# io-board-d-6.net
KiCad netlist of a schematic drawn in EAGLE
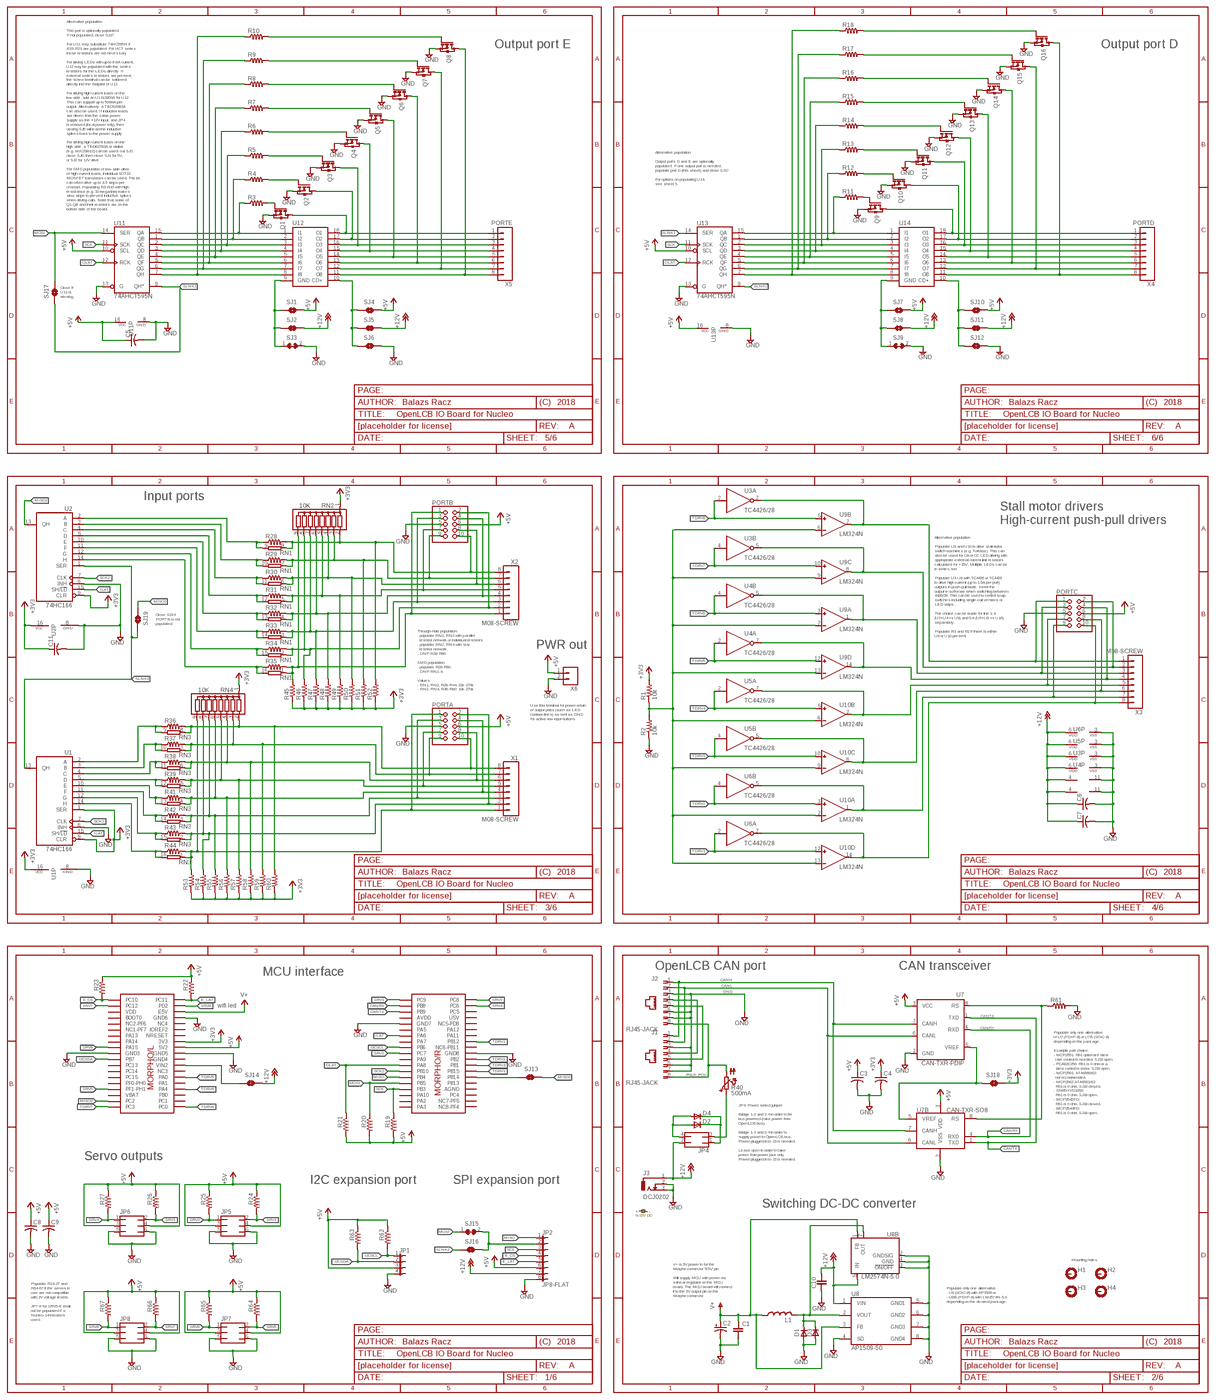
[diagram p0: schematic, sheet 1, overview]
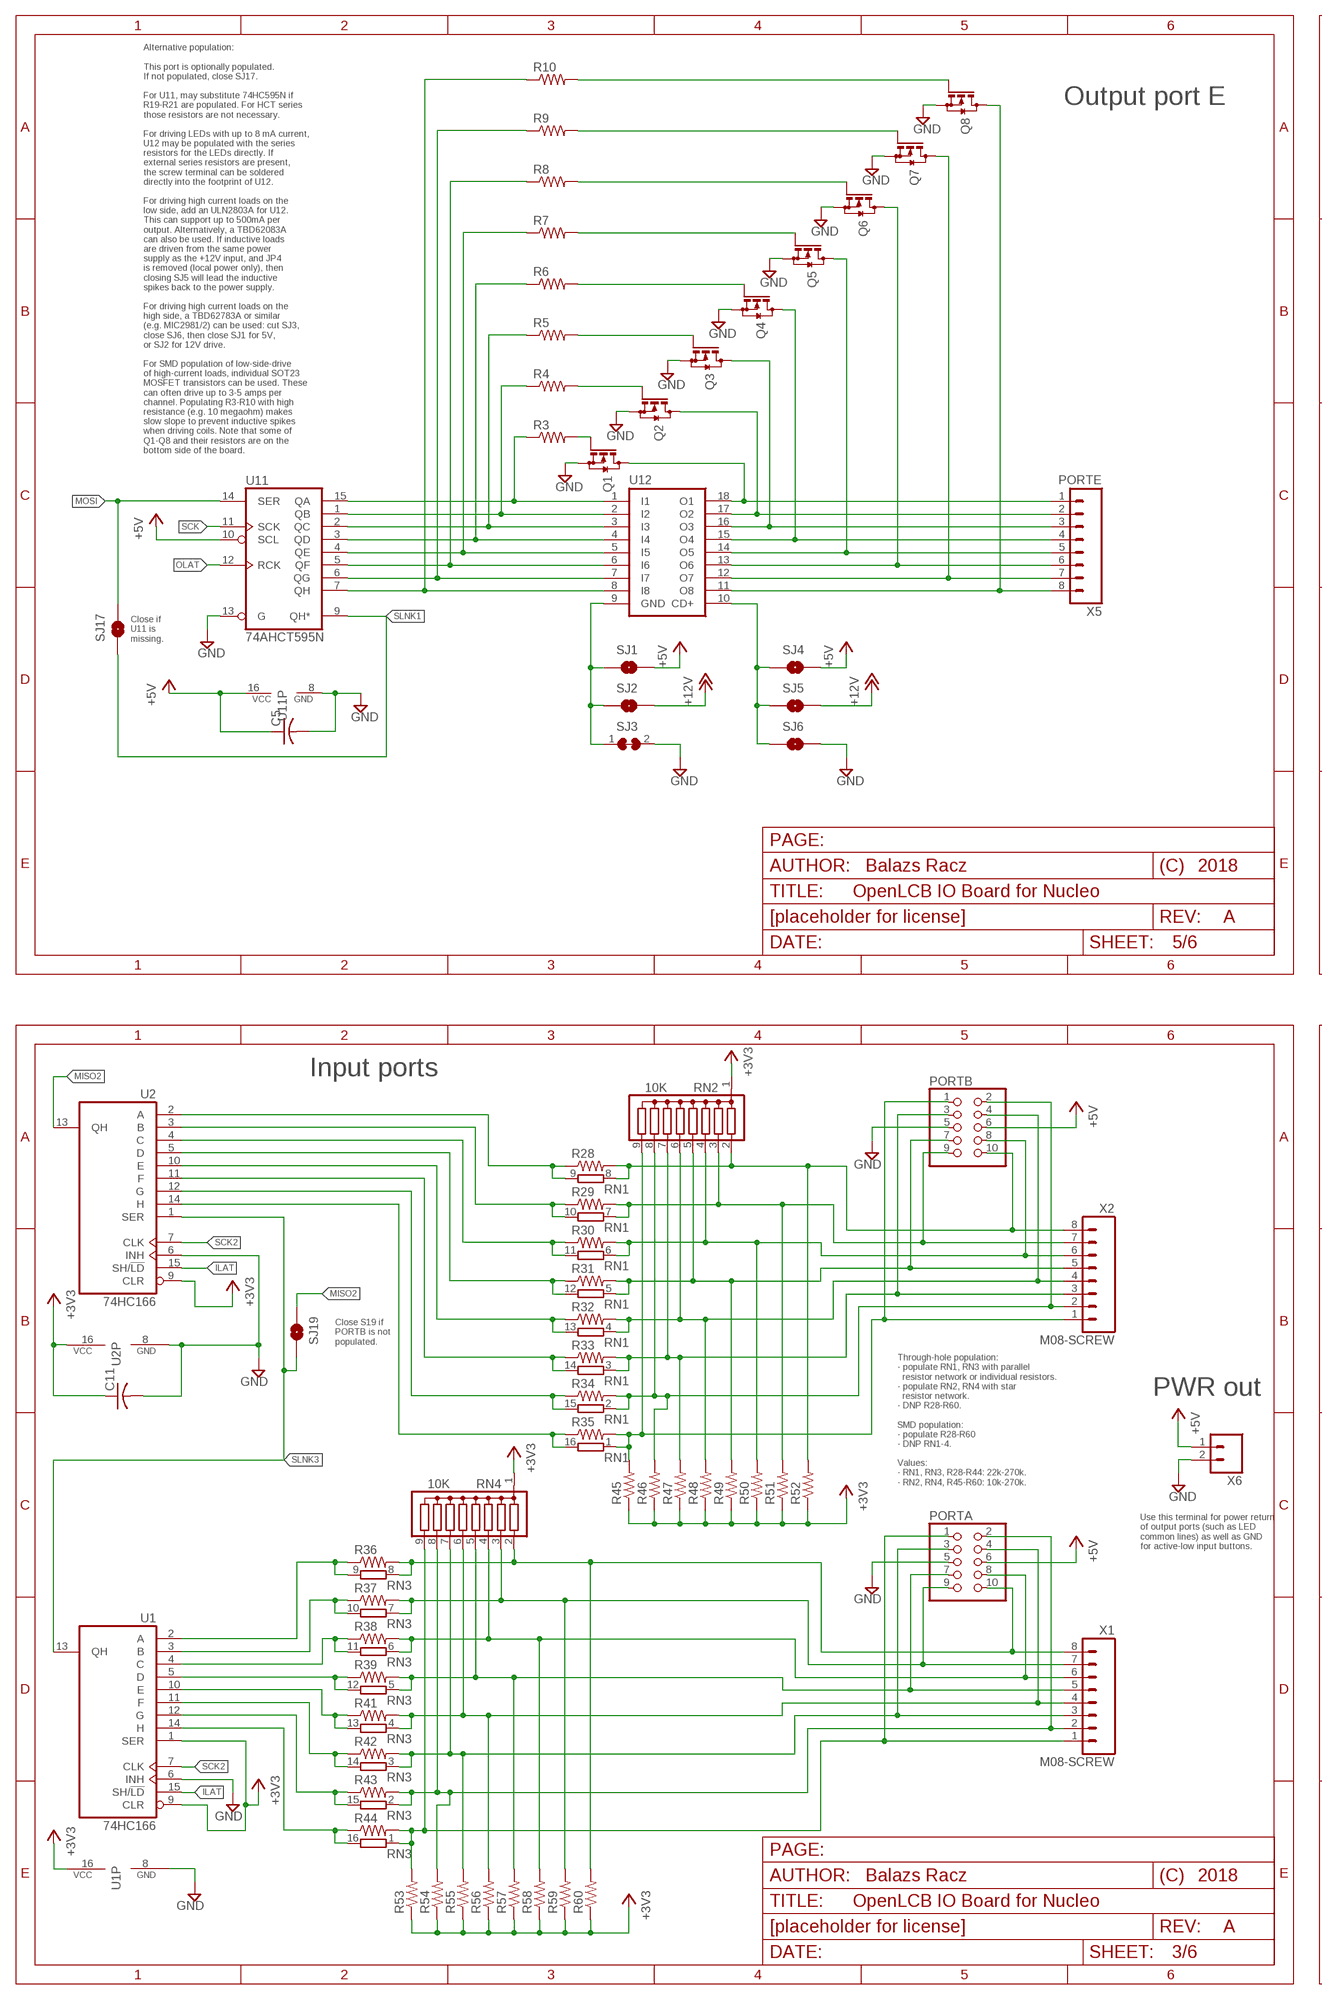
[diagram p1: schematic, sheet 1, part 1 of 4]
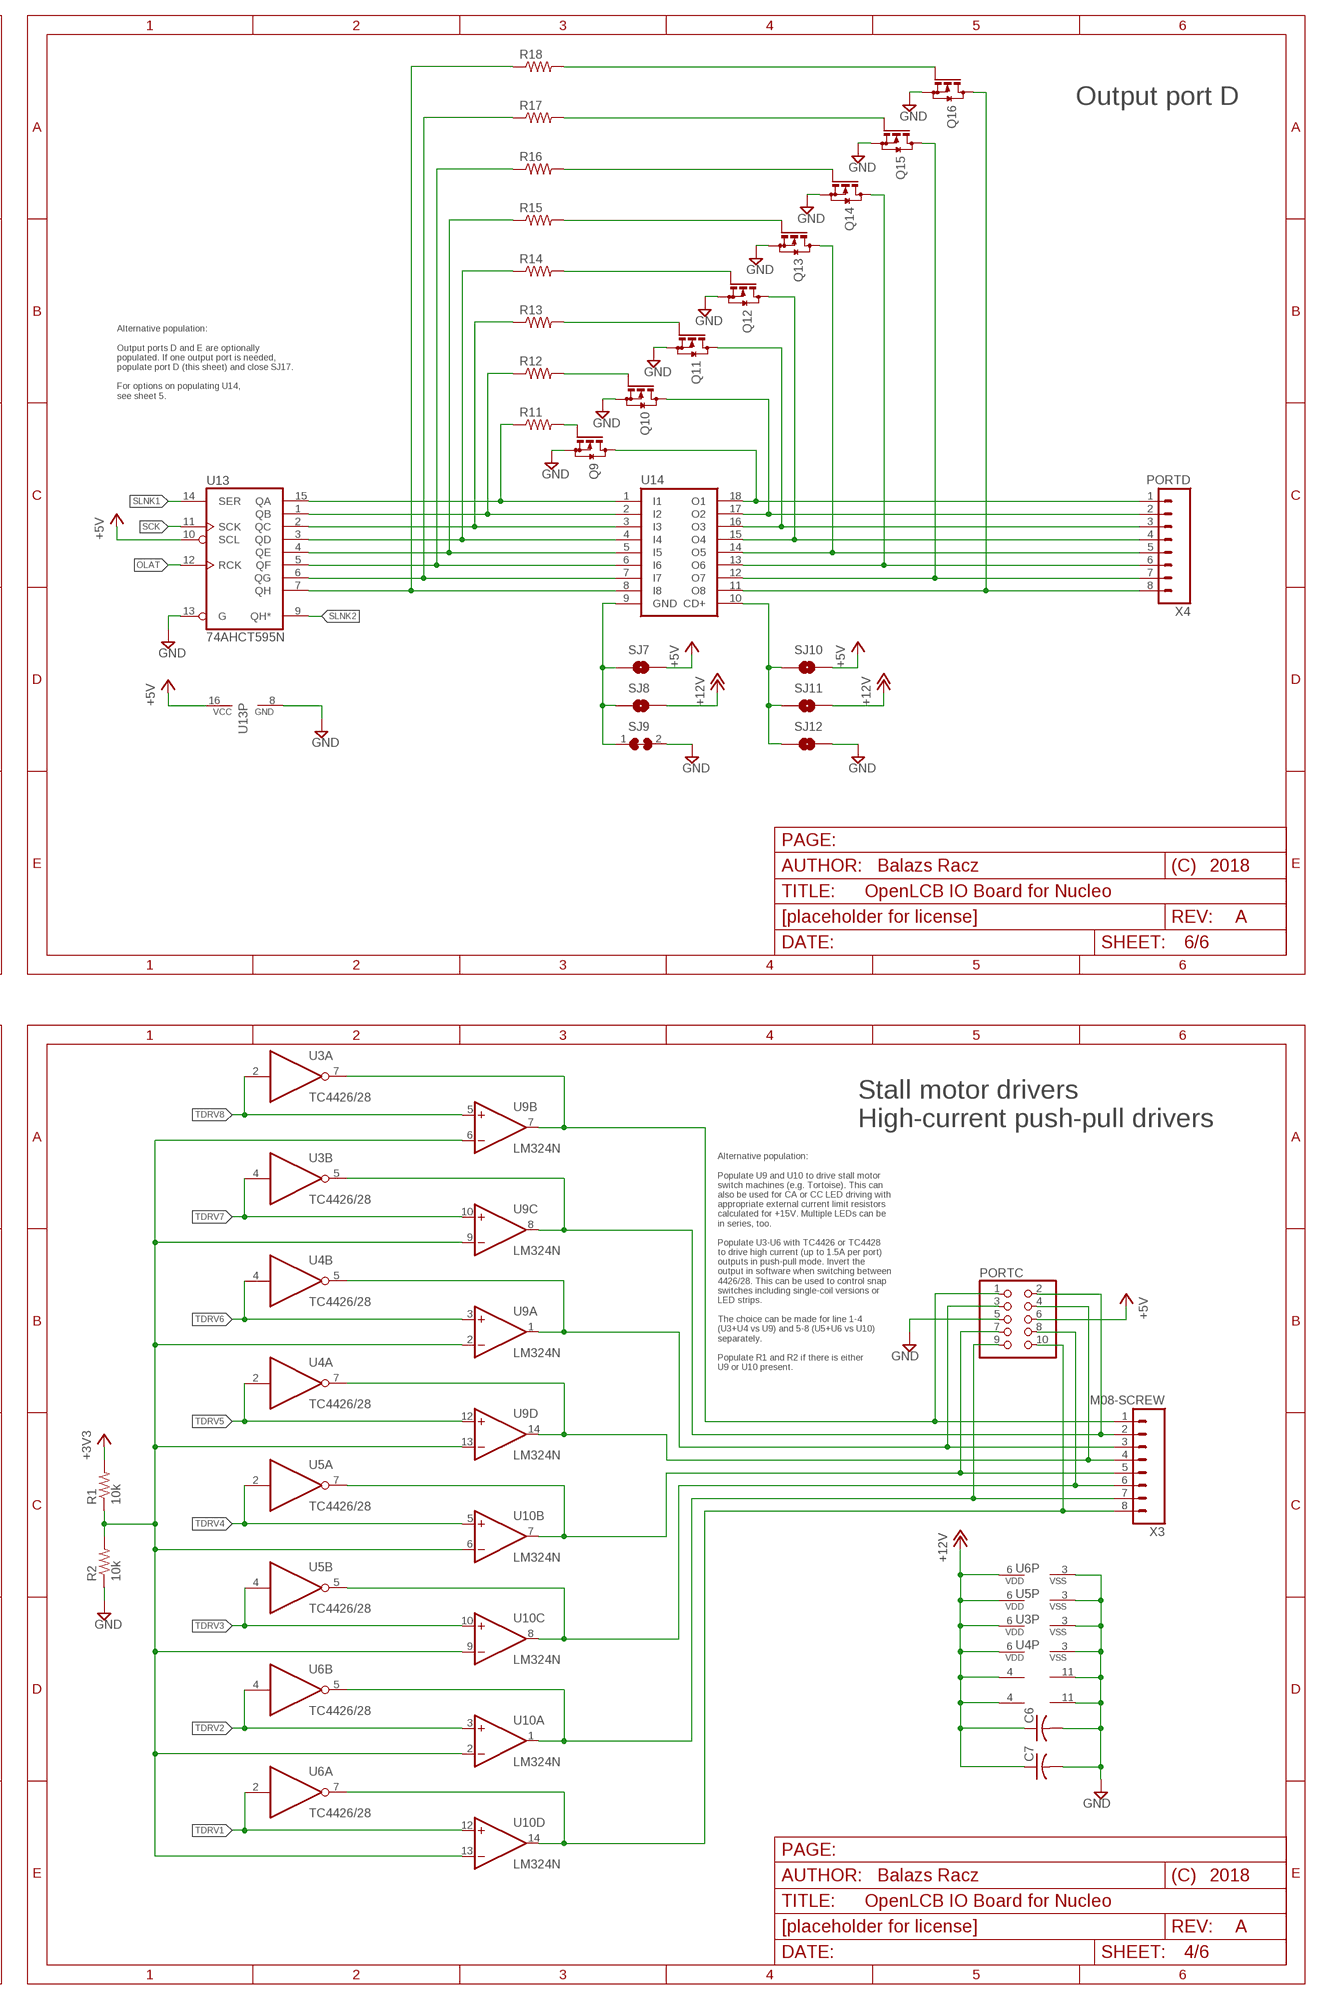
[diagram p2: schematic, sheet 1, part 2 of 4]
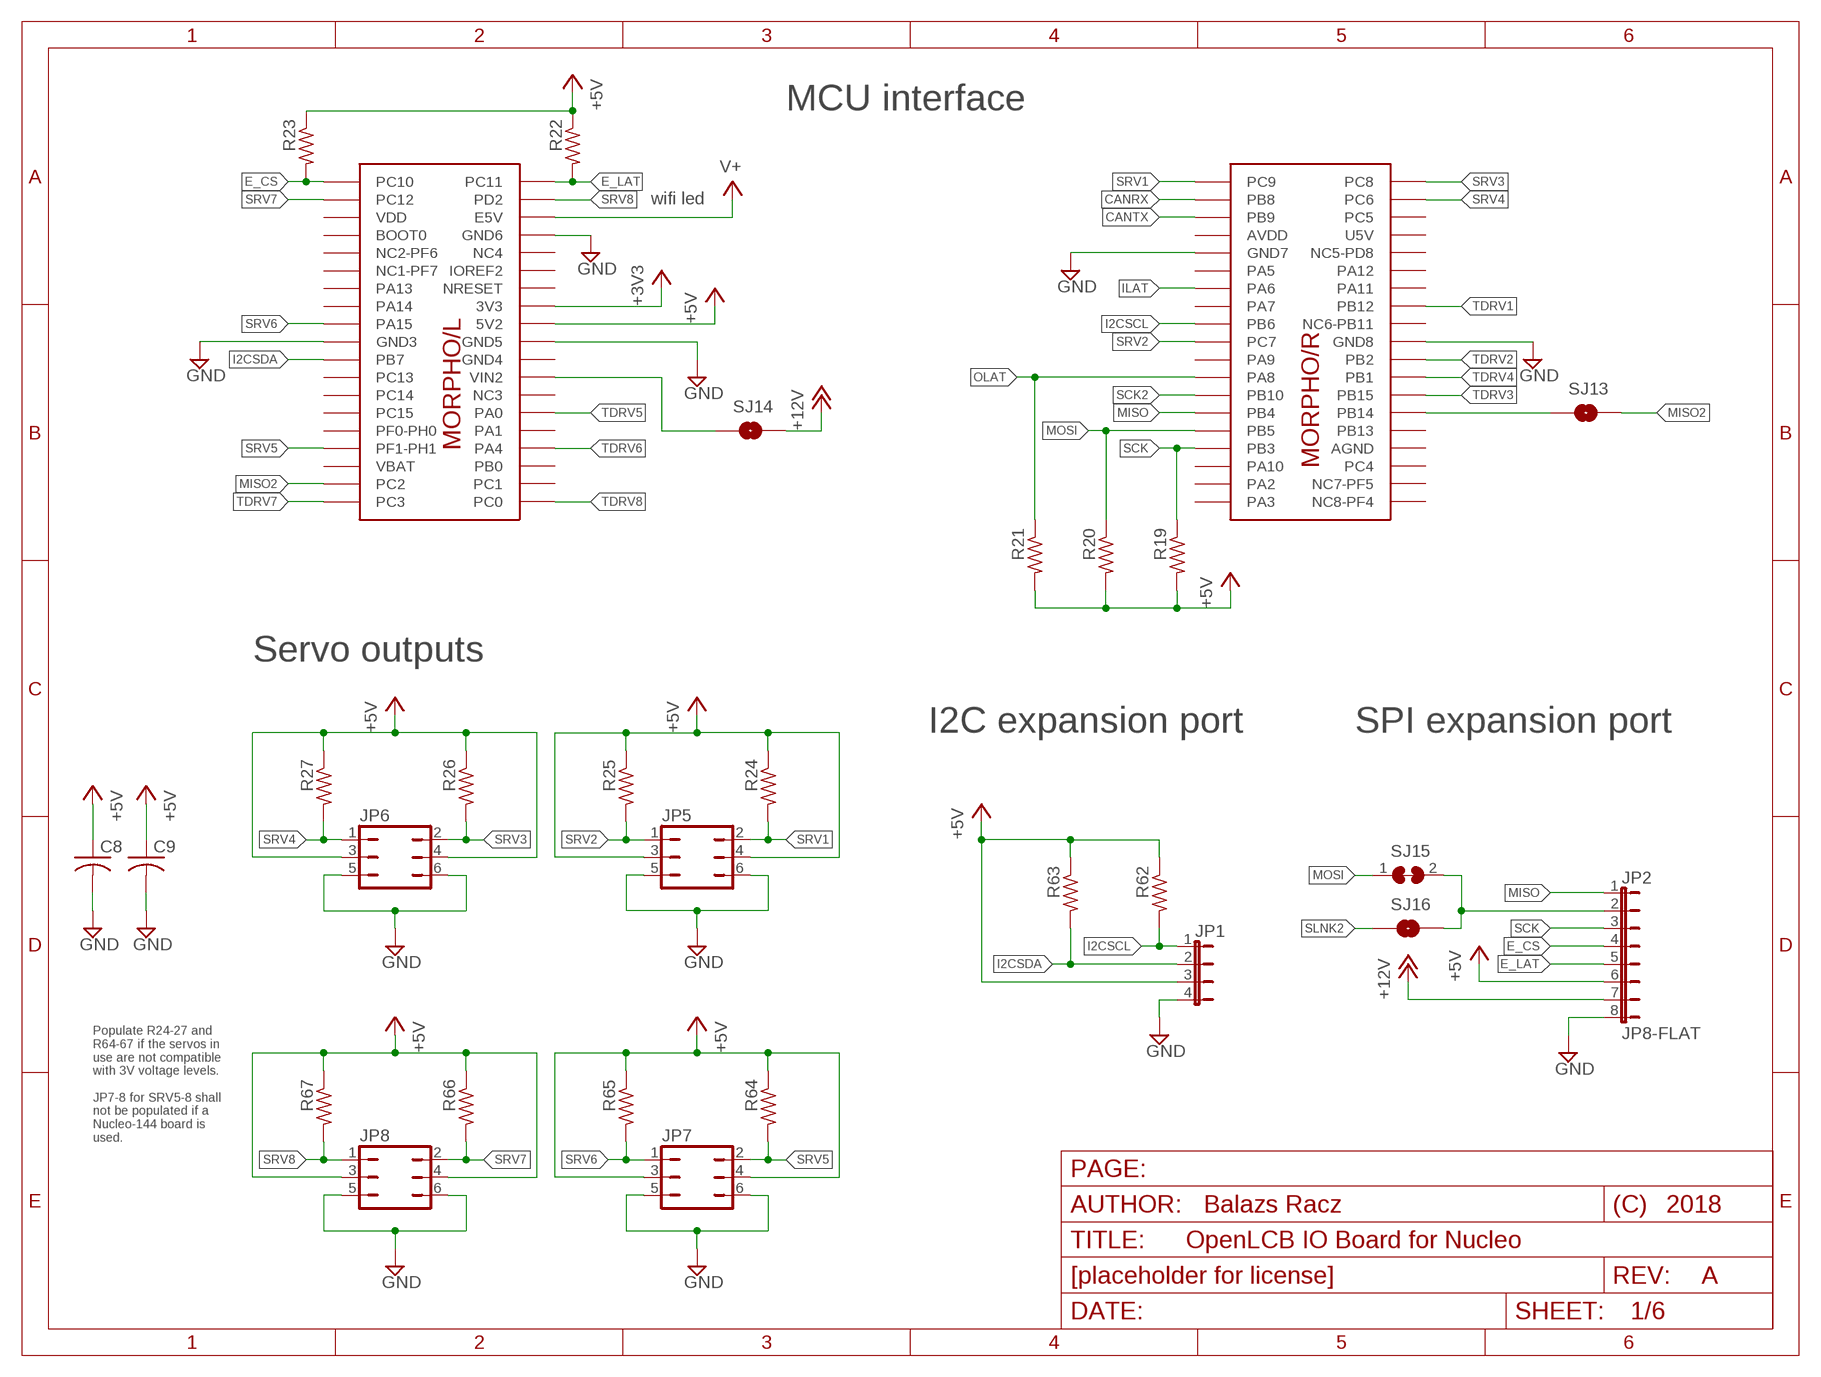
[diagram p3: schematic, sheet 1, part 3 of 4]
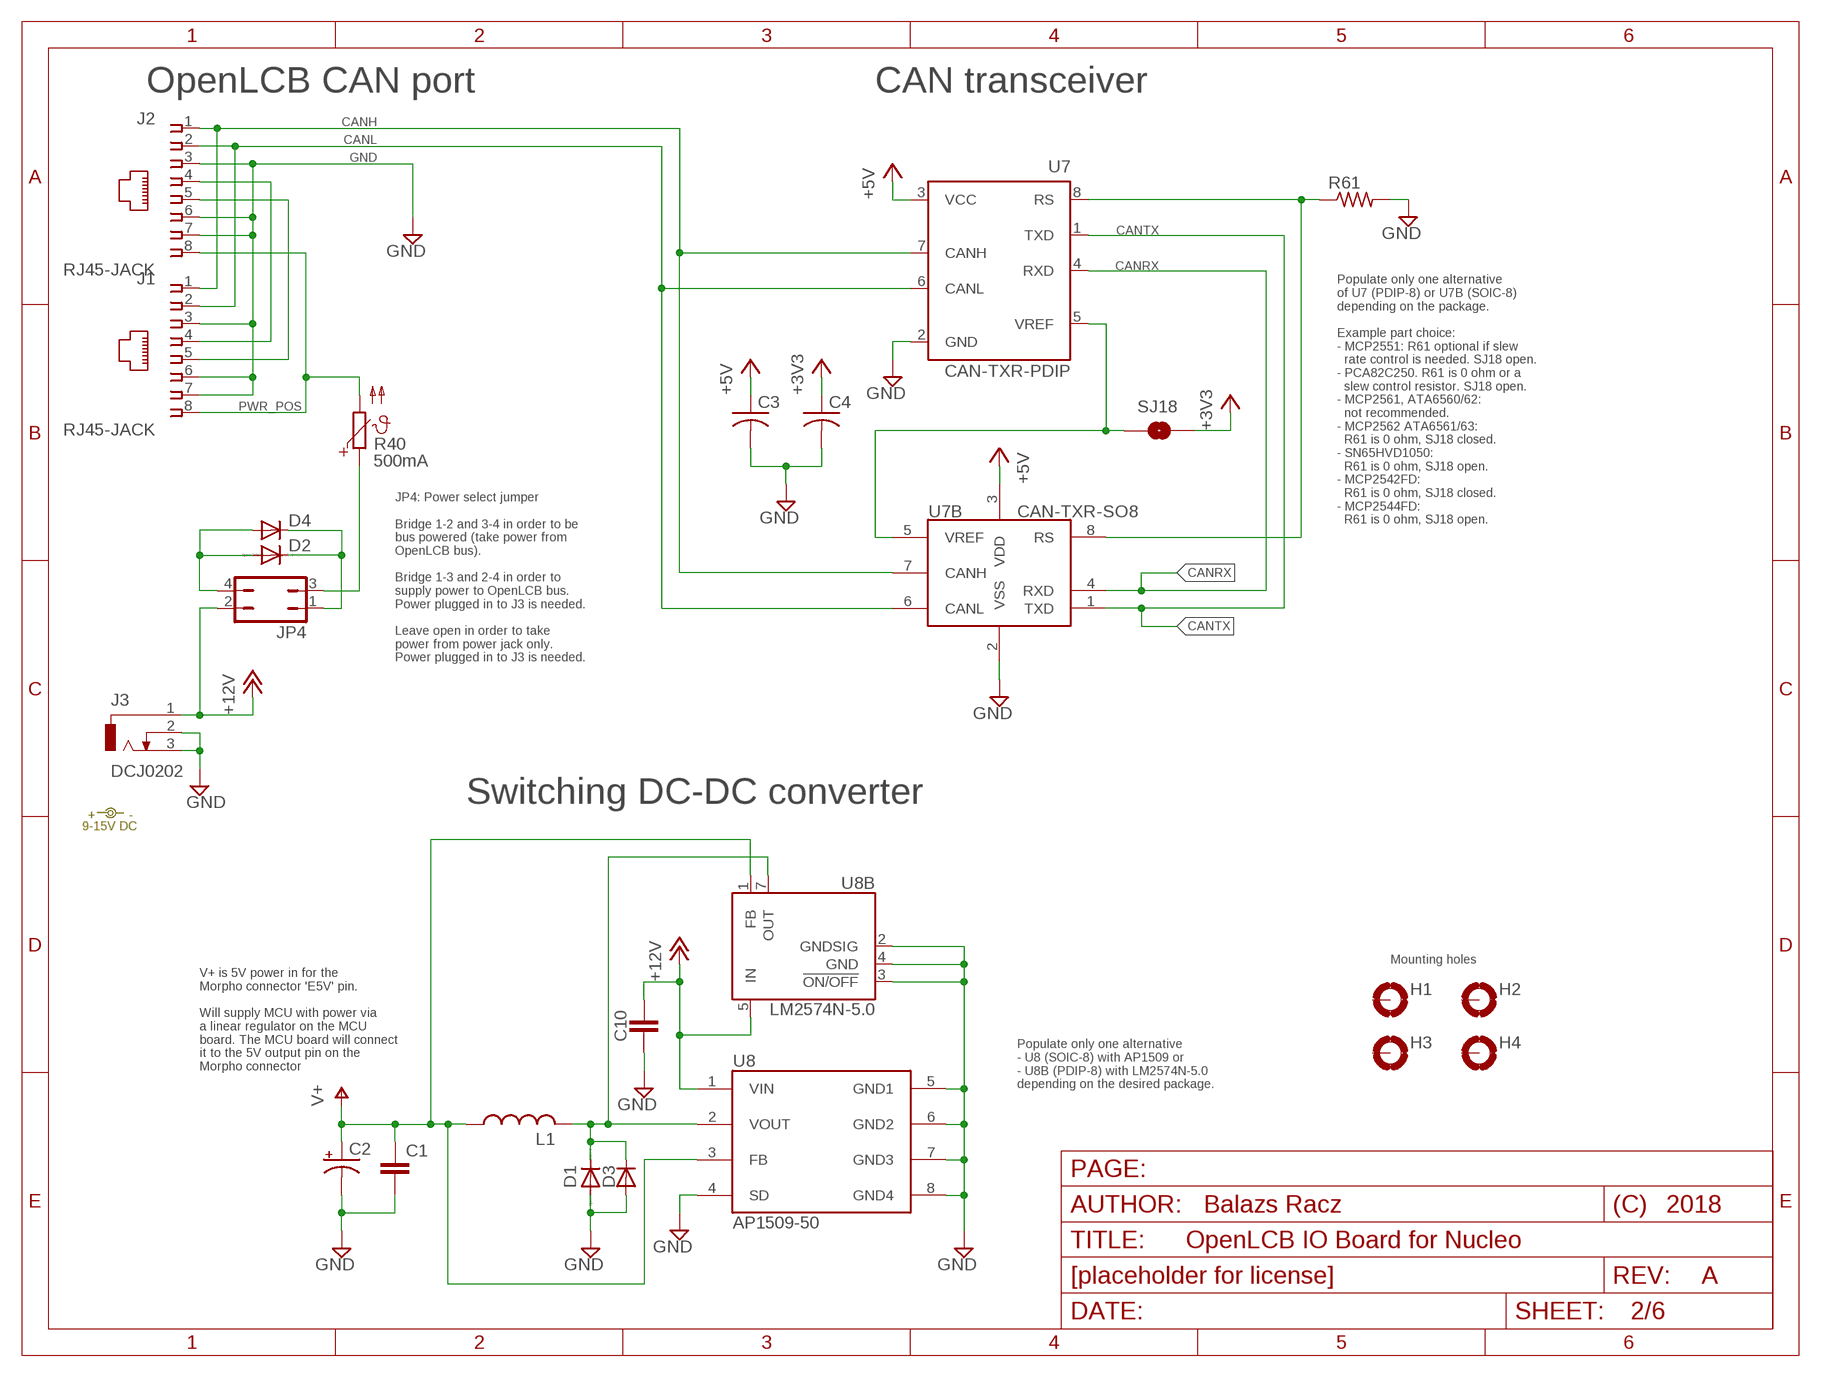
[diagram p4: schematic, sheet 1, part 4 of 4]

(export (version "E")
  (design (tool "Eeschema 10.0.6"))
  (components
    (comp (ref "+12V")
      (value "9-15V DC")
      (footprint "eagle-import:POWER_USAGE")
      (libsource (lib "eagle-import") (part "DOC-POWER_LABEL"))
    )
    (comp (ref "C1")
      (value "C-EUC1206")
      (footprint "eagle-import:C1206")
      (libsource (lib "eagle-import") (part "C-EUC1206"))
    )
    (comp (ref "C2")
      (value "CPOL-USE2.5-5")
      (footprint "eagle-import:E2,5-5")
      (libsource (lib "eagle-import") (part "CPOL-USE2.5-5"))
    )
    (comp (ref "C3")
      (value "C-USC0805")
      (footprint "eagle-import:C0805")
      (libsource (lib "eagle-import") (part "C-USC0805"))
    )
    (comp (ref "C4")
      (value "C-USC0805")
      (footprint "eagle-import:C0805")
      (libsource (lib "eagle-import") (part "C-USC0805"))
    )
    (comp (ref "C5")
      (value "C-USC0805")
      (footprint "eagle-import:C0805")
      (libsource (lib "eagle-import") (part "C-USC0805"))
    )
    (comp (ref "C6")
      (value "C-USC1206")
      (footprint "eagle-import:C1206")
      (libsource (lib "eagle-import") (part "C-USC1206"))
    )
    (comp (ref "C7")
      (value "C-USC1206")
      (footprint "eagle-import:C1206")
      (libsource (lib "eagle-import") (part "C-USC1206"))
    )
    (comp (ref "C8")
      (value "C-USC1206")
      (footprint "eagle-import:C1206")
      (libsource (lib "eagle-import") (part "C-USC1206"))
    )
    (comp (ref "C9")
      (value "C-USC1206")
      (footprint "eagle-import:C1206")
      (libsource (lib "eagle-import") (part "C-USC1206"))
    )
    (comp (ref "C10")
      (value "C-EUC1206")
      (footprint "eagle-import:C1206")
      (libsource (lib "eagle-import") (part "C-EUC1206"))
    )
    (comp (ref "C11")
      (value "C-USC0805")
      (footprint "eagle-import:C0805")
      (libsource (lib "eagle-import") (part "C-USC0805"))
    )
    (comp (ref "D1")
      (value "DIODE-DO41-7.6")
      (footprint "eagle-import:DO41-7.6")
      (libsource (lib "eagle-import") (part "DIODE-DO41-7.6"))
    )
    (comp (ref "D2")
      (value "DIODE-DO41-7.6")
      (footprint "eagle-import:DO41-7.6")
      (libsource (lib "eagle-import") (part "DIODE-DO41-7.6"))
    )
    (comp (ref "D3")
      (value "DIODEDO-214AA-NODOC")
      (footprint "eagle-import:DO214AA-NODOC")
      (libsource (lib "eagle-import") (part "DIODEDO-214AA-NODOC"))
    )
    (comp (ref "D4")
      (value "DIODEDO-214AA-NODOC")
      (footprint "eagle-import:DO214AA-NODOC")
      (libsource (lib "eagle-import") (part "DIODEDO-214AA-NODOC"))
    )
    (comp (ref "H1")
      (value "MOUNT-PAD-ROUND3.3")
      (footprint "eagle-import:3,3-PAD")
      (libsource (lib "eagle-import") (part "MOUNT-PAD-ROUND3.3"))
    )
    (comp (ref "H2")
      (value "MOUNT-PAD-ROUND3.3")
      (footprint "eagle-import:3,3-PAD")
      (libsource (lib "eagle-import") (part "MOUNT-PAD-ROUND3.3"))
    )
    (comp (ref "H3")
      (value "MOUNT-PAD-ROUND3.3")
      (footprint "eagle-import:3,3-PAD")
      (libsource (lib "eagle-import") (part "MOUNT-PAD-ROUND3.3"))
    )
    (comp (ref "H4")
      (value "MOUNT-PAD-ROUND3.3")
      (footprint "eagle-import:3,3-PAD")
      (libsource (lib "eagle-import") (part "MOUNT-PAD-ROUND3.3"))
    )
    (comp (ref "J1")
      (value "RJ45-JACK")
      (footprint "eagle-import:RJ45-PULSE-E5J88")
      (libsource (lib "eagle-import") (part "RJ45-JACKRJ45-PULSE-E5J00"))
    )
    (comp (ref "J2")
      (value "RJ45-JACK")
      (footprint "eagle-import:RJ45-PULSE-E5J88")
      (libsource (lib "eagle-import") (part "RJ45-JACKRJ45-PULSE-E5J00"))
    )
    (comp (ref "J3")
      (value "DCJ0202")
      (footprint "eagle-import:DCJ0202")
      (libsource (lib "eagle-import") (part "DCJ0202"))
    )
    (comp (ref "JP1")
      (value "JP4-FLAT")
      (footprint "eagle-import:JP4F")
      (libsource (lib "eagle-import") (part "JP4-FLAT"))
    )
    (comp (ref "JP2")
      (value "JP8-FLAT")
      (footprint "eagle-import:JP8F")
      (libsource (lib "eagle-import") (part "JP8-FLAT"))
    )
    (comp (ref "JP4")
      (value "JP2Q")
      (footprint "eagle-import:JP2Q")
      (libsource (lib "eagle-import") (part "JP2Q"))
    )
    (comp (ref "JP5")
      (value "JP3Q")
      (footprint "eagle-import:JP3Q")
      (libsource (lib "eagle-import") (part "JP3Q"))
    )
    (comp (ref "JP6")
      (value "JP3Q")
      (footprint "eagle-import:JP3Q")
      (libsource (lib "eagle-import") (part "JP3Q"))
    )
    (comp (ref "JP7")
      (value "JP3Q")
      (footprint "eagle-import:JP3Q")
      (libsource (lib "eagle-import") (part "JP3Q"))
    )
    (comp (ref "JP8")
      (value "JP3Q")
      (footprint "eagle-import:JP3Q")
      (libsource (lib "eagle-import") (part "JP3Q"))
    )
    (comp (ref "L1")
      (value "L-US")
      (footprint "eagle-import:L5-8,5")
      (libsource (lib "eagle-import") (part "L-US"))
    )
    (comp (ref "PORTA")
      (value "PINHD-2X5CN")
      (footprint "eagle-import:CON10M")
      (libsource (lib "eagle-import") (part "PINHD-2X5CN"))
    )
    (comp (ref "PORTB")
      (value "PINHD-2X5CN")
      (footprint "eagle-import:CON10M")
      (libsource (lib "eagle-import") (part "PINHD-2X5CN"))
    )
    (comp (ref "PORTC")
      (value "PINHD-2X5CN")
      (footprint "eagle-import:CON10M")
      (libsource (lib "eagle-import") (part "PINHD-2X5CN"))
    )
    (comp (ref "Q1")
      (value "BSS123")
      (footprint "eagle-import:SOT23")
      (libsource (lib "eagle-import") (part "BSS123"))
    )
    (comp (ref "Q2")
      (value "BSS123")
      (footprint "eagle-import:SOT23")
      (libsource (lib "eagle-import") (part "BSS123"))
    )
    (comp (ref "Q3")
      (value "BSS123")
      (footprint "eagle-import:SOT23")
      (libsource (lib "eagle-import") (part "BSS123"))
    )
    (comp (ref "Q4")
      (value "BSS123")
      (footprint "eagle-import:SOT23")
      (libsource (lib "eagle-import") (part "BSS123"))
    )
    (comp (ref "Q5")
      (value "BSS123")
      (footprint "eagle-import:SOT23")
      (libsource (lib "eagle-import") (part "BSS123"))
    )
    (comp (ref "Q6")
      (value "BSS123")
      (footprint "eagle-import:SOT23")
      (libsource (lib "eagle-import") (part "BSS123"))
    )
    (comp (ref "Q7")
      (value "BSS123")
      (footprint "eagle-import:SOT23")
      (libsource (lib "eagle-import") (part "BSS123"))
    )
    (comp (ref "Q8")
      (value "BSS123")
      (footprint "eagle-import:SOT23")
      (libsource (lib "eagle-import") (part "BSS123"))
    )
    (comp (ref "Q9")
      (value "BSS123")
      (footprint "eagle-import:SOT23")
      (libsource (lib "eagle-import") (part "BSS123"))
    )
    (comp (ref "Q10")
      (value "BSS123")
      (footprint "eagle-import:SOT23")
      (libsource (lib "eagle-import") (part "BSS123"))
    )
    (comp (ref "Q11")
      (value "BSS123")
      (footprint "eagle-import:SOT23")
      (libsource (lib "eagle-import") (part "BSS123"))
    )
    (comp (ref "Q12")
      (value "BSS123")
      (footprint "eagle-import:SOT23")
      (libsource (lib "eagle-import") (part "BSS123"))
    )
    (comp (ref "Q13")
      (value "BSS123")
      (footprint "eagle-import:SOT23")
      (libsource (lib "eagle-import") (part "BSS123"))
    )
    (comp (ref "Q14")
      (value "BSS123")
      (footprint "eagle-import:SOT23")
      (libsource (lib "eagle-import") (part "BSS123"))
    )
    (comp (ref "Q15")
      (value "BSS123")
      (footprint "eagle-import:SOT23")
      (libsource (lib "eagle-import") (part "BSS123"))
    )
    (comp (ref "Q16")
      (value "BSS123")
      (footprint "eagle-import:SOT23")
      (libsource (lib "eagle-import") (part "BSS123"))
    )
    (comp (ref "R1")
      (value "10k")
      (footprint "eagle-import:R0805")
      (libsource (lib "eagle-import") (part "R-US_R0805"))
    )
    (comp (ref "R2")
      (value "10k")
      (footprint "eagle-import:R0805")
      (libsource (lib "eagle-import") (part "R-US_R0805"))
    )
    (comp (ref "R3")
      (value "R-US_R0603")
      (footprint "eagle-import:R0603")
      (libsource (lib "eagle-import") (part "R-US_R0603"))
    )
    (comp (ref "R4")
      (value "R-US_R0603")
      (footprint "eagle-import:R0603")
      (libsource (lib "eagle-import") (part "R-US_R0603"))
    )
    (comp (ref "R5")
      (value "R-US_R0603")
      (footprint "eagle-import:R0603")
      (libsource (lib "eagle-import") (part "R-US_R0603"))
    )
    (comp (ref "R6")
      (value "R-US_R0603")
      (footprint "eagle-import:R0603")
      (libsource (lib "eagle-import") (part "R-US_R0603"))
    )
    (comp (ref "R7")
      (value "R-US_R0603")
      (footprint "eagle-import:R0603")
      (libsource (lib "eagle-import") (part "R-US_R0603"))
    )
    (comp (ref "R8")
      (value "R-US_R0603")
      (footprint "eagle-import:R0603")
      (libsource (lib "eagle-import") (part "R-US_R0603"))
    )
    (comp (ref "R9")
      (value "R-US_R0603")
      (footprint "eagle-import:R0603")
      (libsource (lib "eagle-import") (part "R-US_R0603"))
    )
    (comp (ref "R10")
      (value "R-US_R0603")
      (footprint "eagle-import:R0603")
      (libsource (lib "eagle-import") (part "R-US_R0603"))
    )
    (comp (ref "R11")
      (value "R-US_R0603")
      (footprint "eagle-import:R0603")
      (libsource (lib "eagle-import") (part "R-US_R0603"))
    )
    (comp (ref "R12")
      (value "R-US_R0603")
      (footprint "eagle-import:R0603")
      (libsource (lib "eagle-import") (part "R-US_R0603"))
    )
    (comp (ref "R13")
      (value "R-US_R0603")
      (footprint "eagle-import:R0603")
      (libsource (lib "eagle-import") (part "R-US_R0603"))
    )
    (comp (ref "R14")
      (value "R-US_R0603")
      (footprint "eagle-import:R0603")
      (libsource (lib "eagle-import") (part "R-US_R0603"))
    )
    (comp (ref "R15")
      (value "R-US_R0603")
      (footprint "eagle-import:R0603")
      (libsource (lib "eagle-import") (part "R-US_R0603"))
    )
    (comp (ref "R16")
      (value "R-US_R0603")
      (footprint "eagle-import:R0603")
      (libsource (lib "eagle-import") (part "R-US_R0603"))
    )
    (comp (ref "R17")
      (value "R-US_R0603")
      (footprint "eagle-import:R0603")
      (libsource (lib "eagle-import") (part "R-US_R0603"))
    )
    (comp (ref "R18")
      (value "R-US_R0603")
      (footprint "eagle-import:R0603")
      (libsource (lib "eagle-import") (part "R-US_R0603"))
    )
    (comp (ref "R19")
      (value "R-US_R0805")
      (footprint "eagle-import:R0805")
      (libsource (lib "eagle-import") (part "rcl_334_R-US_R0805"))
    )
    (comp (ref "R20")
      (value "R-US_R0805")
      (footprint "eagle-import:R0805")
      (libsource (lib "eagle-import") (part "rcl_334_R-US_R0805"))
    )
    (comp (ref "R21")
      (value "R-US_R0805")
      (footprint "eagle-import:R0805")
      (libsource (lib "eagle-import") (part "rcl_334_R-US_R0805"))
    )
    (comp (ref "R22")
      (value "R-US_R0805")
      (footprint "eagle-import:R0805")
      (libsource (lib "eagle-import") (part "rcl_334_R-US_R0805"))
    )
    (comp (ref "R23")
      (value "R-US_R0805")
      (footprint "eagle-import:R0805")
      (libsource (lib "eagle-import") (part "rcl_334_R-US_R0805"))
    )
    (comp (ref "R24")
      (value "R-US_R0805")
      (footprint "eagle-import:R0805")
      (libsource (lib "eagle-import") (part "rcl_334_R-US_R0805"))
    )
    (comp (ref "R25")
      (value "R-US_R0805")
      (footprint "eagle-import:R0805")
      (libsource (lib "eagle-import") (part "rcl_334_R-US_R0805"))
    )
    (comp (ref "R26")
      (value "R-US_R0805")
      (footprint "eagle-import:R0805")
      (libsource (lib "eagle-import") (part "rcl_334_R-US_R0805"))
    )
    (comp (ref "R27")
      (value "R-US_R0805")
      (footprint "eagle-import:R0805")
      (libsource (lib "eagle-import") (part "rcl_334_R-US_R0805"))
    )
    (comp (ref "R28")
      (value "R-US_R0603")
      (footprint "eagle-import:R0603")
      (libsource (lib "eagle-import") (part "rcl_334_R-US_R0603"))
    )
    (comp (ref "R29")
      (value "R-US_R0603")
      (footprint "eagle-import:R0603")
      (libsource (lib "eagle-import") (part "rcl_334_R-US_R0603"))
    )
    (comp (ref "R30")
      (value "R-US_R0603")
      (footprint "eagle-import:R0603")
      (libsource (lib "eagle-import") (part "rcl_334_R-US_R0603"))
    )
    (comp (ref "R31")
      (value "R-US_R0603")
      (footprint "eagle-import:R0603")
      (libsource (lib "eagle-import") (part "rcl_334_R-US_R0603"))
    )
    (comp (ref "R32")
      (value "R-US_R0603")
      (footprint "eagle-import:R0603")
      (libsource (lib "eagle-import") (part "rcl_334_R-US_R0603"))
    )
    (comp (ref "R33")
      (value "R-US_R0603")
      (footprint "eagle-import:R0603")
      (libsource (lib "eagle-import") (part "rcl_334_R-US_R0603"))
    )
    (comp (ref "R34")
      (value "R-US_R0603")
      (footprint "eagle-import:R0603")
      (libsource (lib "eagle-import") (part "rcl_334_R-US_R0603"))
    )
    (comp (ref "R35")
      (value "R-US_R0603")
      (footprint "eagle-import:R0603")
      (libsource (lib "eagle-import") (part "rcl_334_R-US_R0603"))
    )
    (comp (ref "R36")
      (value "R-US_R0603")
      (footprint "eagle-import:R0603")
      (libsource (lib "eagle-import") (part "rcl_334_R-US_R0603"))
    )
    (comp (ref "R37")
      (value "R-US_R0603")
      (footprint "eagle-import:R0603")
      (libsource (lib "eagle-import") (part "rcl_334_R-US_R0603"))
    )
    (comp (ref "R38")
      (value "R-US_R0603")
      (footprint "eagle-import:R0603")
      (libsource (lib "eagle-import") (part "rcl_334_R-US_R0603"))
    )
    (comp (ref "R39")
      (value "R-US_R0603")
      (footprint "eagle-import:R0603")
      (libsource (lib "eagle-import") (part "rcl_334_R-US_R0603"))
    )
    (comp (ref "R40")
      (value "500mA")
      (footprint "eagle-import:PTC1812")
      (libsource (lib "eagle-import") (part "PTC_1812"))
    )
    (comp (ref "R41")
      (value "R-US_R0603")
      (footprint "eagle-import:R0603")
      (libsource (lib "eagle-import") (part "rcl_334_R-US_R0603"))
    )
    (comp (ref "R42")
      (value "R-US_R0603")
      (footprint "eagle-import:R0603")
      (libsource (lib "eagle-import") (part "rcl_334_R-US_R0603"))
    )
    (comp (ref "R43")
      (value "R-US_R0603")
      (footprint "eagle-import:R0603")
      (libsource (lib "eagle-import") (part "rcl_334_R-US_R0603"))
    )
    (comp (ref "R44")
      (value "R-US_R0603")
      (footprint "eagle-import:R0603")
      (libsource (lib "eagle-import") (part "rcl_334_R-US_R0603"))
    )
    (comp (ref "R45")
      (value "R-US")
      (footprint "eagle-import:R0603")
      (libsource (lib "eagle-import") (part "R-US"))
    )
    (comp (ref "R46")
      (value "R-US")
      (footprint "eagle-import:R0603")
      (libsource (lib "eagle-import") (part "R-US"))
    )
    (comp (ref "R47")
      (value "R-US")
      (footprint "eagle-import:R0603")
      (libsource (lib "eagle-import") (part "R-US"))
    )
    (comp (ref "R48")
      (value "R-US")
      (footprint "eagle-import:R0603")
      (libsource (lib "eagle-import") (part "R-US"))
    )
    (comp (ref "R49")
      (value "R-US")
      (footprint "eagle-import:R0603")
      (libsource (lib "eagle-import") (part "R-US"))
    )
    (comp (ref "R50")
      (value "R-US")
      (footprint "eagle-import:R0603")
      (libsource (lib "eagle-import") (part "R-US"))
    )
    (comp (ref "R51")
      (value "R-US")
      (footprint "eagle-import:R0603")
      (libsource (lib "eagle-import") (part "R-US"))
    )
    (comp (ref "R52")
      (value "R-US")
      (footprint "eagle-import:R0603")
      (libsource (lib "eagle-import") (part "R-US"))
    )
    (comp (ref "R53")
      (value "R-US")
      (footprint "eagle-import:R0603")
      (libsource (lib "eagle-import") (part "R-US"))
    )
    (comp (ref "R54")
      (value "R-US")
      (footprint "eagle-import:R0603")
      (libsource (lib "eagle-import") (part "R-US"))
    )
    (comp (ref "R55")
      (value "R-US")
      (footprint "eagle-import:R0603")
      (libsource (lib "eagle-import") (part "R-US"))
    )
    (comp (ref "R56")
      (value "R-US")
      (footprint "eagle-import:R0603")
      (libsource (lib "eagle-import") (part "R-US"))
    )
    (comp (ref "R57")
      (value "R-US")
      (footprint "eagle-import:R0603")
      (libsource (lib "eagle-import") (part "R-US"))
    )
    (comp (ref "R58")
      (value "R-US")
      (footprint "eagle-import:R0603")
      (libsource (lib "eagle-import") (part "R-US"))
    )
    (comp (ref "R59")
      (value "R-US")
      (footprint "eagle-import:R0603")
      (libsource (lib "eagle-import") (part "R-US"))
    )
    (comp (ref "R60")
      (value "R-US")
      (footprint "eagle-import:R0603")
      (libsource (lib "eagle-import") (part "R-US"))
    )
    (comp (ref "R61")
      (value "R-US_R0805")
      (footprint "eagle-import:R0805")
      (libsource (lib "eagle-import") (part "rcl_334_R-US_R0805"))
    )
    (comp (ref "R62")
      (value "R-US_R0805")
      (footprint "eagle-import:R0805")
      (libsource (lib "eagle-import") (part "rcl_334_R-US_R0805"))
    )
    (comp (ref "R63")
      (value "R-US_R0805")
      (footprint "eagle-import:R0805")
      (libsource (lib "eagle-import") (part "rcl_334_R-US_R0805"))
    )
    (comp (ref "R64")
      (value "R-US_R0805")
      (footprint "eagle-import:R0805")
      (libsource (lib "eagle-import") (part "rcl_334_R-US_R0805"))
    )
    (comp (ref "R65")
      (value "R-US_R0805")
      (footprint "eagle-import:R0805")
      (libsource (lib "eagle-import") (part "rcl_334_R-US_R0805"))
    )
    (comp (ref "R66")
      (value "R-US_R0805")
      (footprint "eagle-import:R0805")
      (libsource (lib "eagle-import") (part "rcl_334_R-US_R0805"))
    )
    (comp (ref "R67")
      (value "R-US_R0805")
      (footprint "eagle-import:R0805")
      (libsource (lib "eagle-import") (part "rcl_334_R-US_R0805"))
    )
    (comp (ref "RN1")
      (value "8R-P")
      (footprint "eagle-import:DIL16")
      (libsource (lib "eagle-import") (part "8R-P"))
    )
    (comp (ref "RN2")
      (value "10K")
      (footprint "eagle-import:SIL9")
      (libsource (lib "eagle-import") (part "G08R"))
    )
    (comp (ref "RN3")
      (value "8R-P")
      (footprint "eagle-import:DIL16")
      (libsource (lib "eagle-import") (part "8R-P"))
    )
    (comp (ref "RN4")
      (value "10K")
      (footprint "eagle-import:SIL9")
      (libsource (lib "eagle-import") (part "G08R"))
    )
    (comp (ref "SJ1")
      (value "SJRND2")
      (footprint "eagle-import:SJ_RND2")
      (libsource (lib "eagle-import") (part "SJRND2"))
    )
    (comp (ref "SJ2")
      (value "SJRND2")
      (footprint "eagle-import:SJ_RND2")
      (libsource (lib "eagle-import") (part "SJRND2"))
    )
    (comp (ref "SJ3")
      (value "SJ-C")
      (footprint "eagle-import:SJW-C")
      (libsource (lib "eagle-import") (part "SJ-C"))
    )
    (comp (ref "SJ4")
      (value "SJRND2")
      (footprint "eagle-import:SJ_RND2")
      (libsource (lib "eagle-import") (part "SJRND2"))
    )
    (comp (ref "SJ5")
      (value "SJRND2")
      (footprint "eagle-import:SJ_RND2")
      (libsource (lib "eagle-import") (part "SJRND2"))
    )
    (comp (ref "SJ6")
      (value "SJRND2")
      (footprint "eagle-import:SJ_RND2")
      (libsource (lib "eagle-import") (part "SJRND2"))
    )
    (comp (ref "SJ7")
      (value "SJRND2")
      (footprint "eagle-import:SJ_RND2")
      (libsource (lib "eagle-import") (part "SJRND2"))
    )
    (comp (ref "SJ8")
      (value "SJRND2")
      (footprint "eagle-import:SJ_RND2")
      (libsource (lib "eagle-import") (part "SJRND2"))
    )
    (comp (ref "SJ9")
      (value "SJ-C")
      (footprint "eagle-import:SJW-C")
      (libsource (lib "eagle-import") (part "SJ-C"))
    )
    (comp (ref "SJ10")
      (value "SJRND2")
      (footprint "eagle-import:SJ_RND2")
      (libsource (lib "eagle-import") (part "SJRND2"))
    )
    (comp (ref "SJ11")
      (value "SJRND2")
      (footprint "eagle-import:SJ_RND2")
      (libsource (lib "eagle-import") (part "SJRND2"))
    )
    (comp (ref "SJ12")
      (value "SJRND2")
      (footprint "eagle-import:SJ_RND2")
      (libsource (lib "eagle-import") (part "SJRND2"))
    )
    (comp (ref "SJ13")
      (value "SJRND2")
      (footprint "eagle-import:SJ_RND2")
      (libsource (lib "eagle-import") (part "SJRND2"))
    )
    (comp (ref "SJ14")
      (value "SJRND2")
      (footprint "eagle-import:SJ_RND2")
      (libsource (lib "eagle-import") (part "SJRND2"))
    )
    (comp (ref "SJ15")
      (value "SJ-C")
      (footprint "eagle-import:SJW-C")
      (libsource (lib "eagle-import") (part "SJ-C"))
    )
    (comp (ref "SJ16")
      (value "SJRND2")
      (footprint "eagle-import:SJ_RND2")
      (libsource (lib "eagle-import") (part "SJRND2"))
    )
    (comp (ref "SJ17")
      (value "SJRND2")
      (footprint "eagle-import:SJ_RND2")
      (libsource (lib "eagle-import") (part "SJRND2"))
    )
    (comp (ref "SJ18")
      (value "SJRND2")
      (footprint "eagle-import:SJ_RND2")
      (libsource (lib "eagle-import") (part "SJRND2"))
    )
    (comp (ref "SJ19")
      (value "SJRND2")
      (footprint "eagle-import:SJ_RND2")
      (libsource (lib "eagle-import") (part "SJRND2"))
    )
    (comp (ref "U$1")
      (value "NUCLEO_64_GENERIC")
      (footprint "eagle-import:NUCLEO_BRD_BASE64")
      (libsource (lib "eagle-import") (part "NUCLEO_64_GENERIC"))
    )
    (comp (ref "U1")
      (value "74HC166")
      (footprint "eagle-import:DIL16")
      (libsource (lib "eagle-import") (part "74166N"))
    )
    (comp (ref "U2")
      (value "74HC166")
      (footprint "eagle-import:DIL16")
      (libsource (lib "eagle-import") (part "74166N"))
    )
    (comp (ref "U3")
      (value "TC4426/28")
      (footprint "eagle-import:DIL08-LONG")
      (libsource (lib "eagle-import") (part "TC4426APDIP"))
    )
    (comp (ref "U4")
      (value "TC4426/28")
      (footprint "eagle-import:DIL08-LONG")
      (libsource (lib "eagle-import") (part "TC4426APDIP"))
    )
    (comp (ref "U5")
      (value "TC4426/28")
      (footprint "eagle-import:DIL08-LONG")
      (libsource (lib "eagle-import") (part "TC4426APDIP"))
    )
    (comp (ref "U6")
      (value "TC4426/28")
      (footprint "eagle-import:DIL08-LONG")
      (libsource (lib "eagle-import") (part "TC4426APDIP"))
    )
    (comp (ref "U7")
      (value "CAN-TXR-PDIP")
      (footprint "eagle-import:DIL08")
      (libsource (lib "eagle-import") (part "PCA82C250"))
    )
    (comp (ref "U7B")
      (value "CAN-TXR-SO8")
      (footprint "eagle-import:SO-08")
      (libsource (lib "eagle-import") (part "MCP2551-SN"))
    )
    (comp (ref "U8")
      (value "AP1509-50")
      (footprint "eagle-import:SO-08")
      (libsource (lib "eagle-import") (part "AP1509"))
    )
    (comp (ref "U8B")
      (value "LM2574N-5.0")
      (footprint "eagle-import:DIL08")
      (libsource (lib "eagle-import") (part "LM2574?-N5.0"))
    )
    (comp (ref "U9")
      (value "LM324N")
      (footprint "eagle-import:DIL14")
      (libsource (lib "eagle-import") (part "LM324N"))
    )
    (comp (ref "U10")
      (value "LM324N")
      (footprint "eagle-import:DIL14")
      (libsource (lib "eagle-import") (part "LM324N"))
    )
    (comp (ref "U11")
      (value "74AHCT595N")
      (footprint "eagle-import:DIL16")
      (libsource (lib "eagle-import") (part "74595NHCT"))
    )
    (comp (ref "U12")
      (value "ULN2803A")
      (footprint "eagle-import:DIL18-THIN")
      (libsource (lib "eagle-import") (part "ULN2803A"))
    )
    (comp (ref "U13")
      (value "74AHCT595N")
      (footprint "eagle-import:DIL16")
      (libsource (lib "eagle-import") (part "74595NHCT"))
    )
    (comp (ref "U14")
      (value "ULN2803A")
      (footprint "eagle-import:DIL18-THIN")
      (libsource (lib "eagle-import") (part "ULN2803A"))
    )
    (comp (ref "X1")
      (value "M08-SCREW")
      (footprint "eagle-import:1X08_TERMINAL")
      (libsource (lib "eagle-import") (part "M08-SCREW"))
    )
    (comp (ref "X2")
      (value "M08-SCREW")
      (footprint "eagle-import:1X08_TERMINAL")
      (libsource (lib "eagle-import") (part "M08-SCREW"))
    )
    (comp (ref "X3")
      (value "M08-SCREW")
      (footprint "eagle-import:1X08_TERMINAL")
      (libsource (lib "eagle-import") (part "M08-SCREW"))
    )
    (comp (ref "X4")
      (value "PORTD")
      (footprint "eagle-import:1X08_TERMINAL")
      (libsource (lib "eagle-import") (part "M08-SCREW"))
    )
    (comp (ref "X5")
      (value "PORTE")
      (footprint "eagle-import:1X08_TERMINAL")
      (libsource (lib "eagle-import") (part "M08-SCREW"))
    )
    (comp (ref "X6")
      (value "CONNECTOR-M023.5MM-LOCK")
      (footprint "eagle-import:SCREWTERMINAL-3.5MM-2_LOCK")
      (libsource (lib "eagle-import") (part "CONNECTOR-M023.5MM-LOCK"))
    )
  )
  (nets
    (net (code "1") (name "+3V3") (class "Default")
      (node (ref "C11") (pin "1") (pinfunction "1_1") (pintype "passive"))
      (node (ref "C4") (pin "1") (pinfunction "1_1") (pintype "passive"))
      (node (ref "R1") (pin "2") (pinfunction "2_2") (pintype "passive"))
      (node (ref "R45") (pin "1") (pinfunction "1_1") (pintype "passive"))
      (node (ref "R46") (pin "1") (pinfunction "1_1") (pintype "passive"))
      (node (ref "R47") (pin "1") (pinfunction "1_1") (pintype "passive"))
      (node (ref "R48") (pin "1") (pinfunction "1_1") (pintype "passive"))
      (node (ref "R49") (pin "1") (pinfunction "1_1") (pintype "passive"))
      (node (ref "R50") (pin "1") (pinfunction "1_1") (pintype "passive"))
      (node (ref "R51") (pin "1") (pinfunction "1_1") (pintype "passive"))
      (node (ref "R52") (pin "1") (pinfunction "1_1") (pintype "passive"))
      (node (ref "R53") (pin "1") (pinfunction "1_1") (pintype "passive"))
      (node (ref "R54") (pin "1") (pinfunction "1_1") (pintype "passive"))
      (node (ref "R55") (pin "1") (pinfunction "1_1") (pintype "passive"))
      (node (ref "R56") (pin "1") (pinfunction "1_1") (pintype "passive"))
      (node (ref "R57") (pin "1") (pinfunction "1_1") (pintype "passive"))
      (node (ref "R58") (pin "1") (pinfunction "1_1") (pintype "passive"))
      (node (ref "R59") (pin "1") (pinfunction "1_1") (pintype "passive"))
      (node (ref "R60") (pin "1") (pinfunction "1_1") (pintype "passive"))
      (node (ref "RN2") (pin "1") (pinfunction "1_1") (pintype "passive"))
      (node (ref "RN4") (pin "1") (pinfunction "1_1") (pintype "passive"))
      (node (ref "SJ18") (pin "P$1") (pinfunction "1_P$1") (pintype "passive"))
      (node (ref "U$1") (pin "3V3") (pinfunction "3V3_3V3") (pintype "power_in"))
      (node (ref "U1") (pin "1") (pinfunction "SER_1") (pintype "input"))
      (node (ref "U1") (pin "16") (pinfunction "VCC_16") (pintype "power_in"))
      (node (ref "U1") (pin "9") (pinfunction "CLR_9") (pintype "input"))
      (node (ref "U2") (pin "16") (pinfunction "VCC_16") (pintype "power_in"))
      (node (ref "U2") (pin "9") (pinfunction "CLR_9") (pintype "input"))
    )
    (net (code "2") (name "+5V") (class "Default")
      (node (ref "C3") (pin "1") (pinfunction "1_1") (pintype "passive"))
      (node (ref "C5") (pin "1") (pinfunction "1_1") (pintype "passive"))
      (node (ref "C8") (pin "1") (pinfunction "1_1") (pintype "passive"))
      (node (ref "C9") (pin "1") (pinfunction "1_1") (pintype "passive"))
      (node (ref "JP1") (pin "3") (pinfunction "3_3") (pintype "passive"))
      (node (ref "JP2") (pin "6") (pinfunction "6_6") (pintype "passive"))
      (node (ref "JP5") (pin "3") (pinfunction "3_3") (pintype "passive"))
      (node (ref "JP5") (pin "4") (pinfunction "4_4") (pintype "passive"))
      (node (ref "JP6") (pin "3") (pinfunction "3_3") (pintype "passive"))
      (node (ref "JP6") (pin "4") (pinfunction "4_4") (pintype "passive"))
      (node (ref "JP7") (pin "3") (pinfunction "3_3") (pintype "passive"))
      (node (ref "JP7") (pin "4") (pinfunction "4_4") (pintype "passive"))
      (node (ref "JP8") (pin "3") (pinfunction "3_3") (pintype "passive"))
      (node (ref "JP8") (pin "4") (pinfunction "4_4") (pintype "passive"))
      (node (ref "PORTA") (pin "6") (pinfunction "6_6") (pintype "passive"))
      (node (ref "PORTB") (pin "6") (pinfunction "6_6") (pintype "passive"))
      (node (ref "PORTC") (pin "6") (pinfunction "6_6") (pintype "passive"))
      (node (ref "R19") (pin "2") (pinfunction "2_2") (pintype "passive"))
      (node (ref "R20") (pin "2") (pinfunction "2_2") (pintype "passive"))
      (node (ref "R21") (pin "2") (pinfunction "2_2") (pintype "passive"))
      (node (ref "R22") (pin "1") (pinfunction "1_1") (pintype "passive"))
      (node (ref "R23") (pin "1") (pinfunction "1_1") (pintype "passive"))
      (node (ref "R24") (pin "1") (pinfunction "1_1") (pintype "passive"))
      (node (ref "R25") (pin "1") (pinfunction "1_1") (pintype "passive"))
      (node (ref "R26") (pin "1") (pinfunction "1_1") (pintype "passive"))
      (node (ref "R27") (pin "1") (pinfunction "1_1") (pintype "passive"))
      (node (ref "R62") (pin "1") (pinfunction "1_1") (pintype "passive"))
      (node (ref "R63") (pin "1") (pinfunction "1_1") (pintype "passive"))
      (node (ref "R64") (pin "1") (pinfunction "1_1") (pintype "passive"))
      (node (ref "R65") (pin "1") (pinfunction "1_1") (pintype "passive"))
      (node (ref "R66") (pin "1") (pinfunction "1_1") (pintype "passive"))
      (node (ref "R67") (pin "1") (pinfunction "1_1") (pintype "passive"))
      (node (ref "SJ1") (pin "P$2") (pinfunction "2_P$2") (pintype "passive"))
      (node (ref "SJ10") (pin "P$2") (pinfunction "2_P$2") (pintype "passive"))
      (node (ref "SJ4") (pin "P$2") (pinfunction "2_P$2") (pintype "passive"))
      (node (ref "SJ7") (pin "P$2") (pinfunction "2_P$2") (pintype "passive"))
      (node (ref "U$1") (pin "5V2") (pinfunction "5V2_5V2") (pintype "power_in"))
      (node (ref "U11") (pin "10") (pinfunction "SCL_10") (pintype "input"))
      (node (ref "U11") (pin "16") (pinfunction "VCC_16") (pintype "power_in"))
      (node (ref "U13") (pin "10") (pinfunction "SCL_10") (pintype "input"))
      (node (ref "U13") (pin "16") (pinfunction "VCC_16") (pintype "power_in"))
      (node (ref "U7") (pin "3") (pinfunction "VCC_3") (pintype "power_in"))
      (node (ref "U7B") (pin "3") (pinfunction "VDD_3") (pintype "power_in"))
      (node (ref "X6") (pin "1") (pinfunction "1_1") (pintype "passive"))
    )
    (net (code "3") (name "+12V") (class "Default")
      (node (ref "C10") (pin "1") (pinfunction "1_1") (pintype "passive"))
      (node (ref "C6") (pin "1") (pinfunction "1_1") (pintype "passive"))
      (node (ref "C7") (pin "1") (pinfunction "1_1") (pintype "passive"))
      (node (ref "J3") (pin "1") (pinfunction "1_1") (pintype "passive"))
      (node (ref "JP2") (pin "7") (pinfunction "7_7") (pintype "passive"))
      (node (ref "JP4") (pin "2") (pinfunction "2_2") (pintype "passive"))
      (node (ref "SJ11") (pin "P$2") (pinfunction "2_P$2") (pintype "passive"))
      (node (ref "SJ14") (pin "P$2") (pinfunction "2_P$2") (pintype "passive"))
      (node (ref "SJ2") (pin "P$2") (pinfunction "2_P$2") (pintype "passive"))
      (node (ref "SJ5") (pin "P$2") (pinfunction "2_P$2") (pintype "passive"))
      (node (ref "SJ8") (pin "P$2") (pinfunction "2_P$2") (pintype "passive"))
      (node (ref "U10") (pin "4") (pinfunction "V+_4") (pintype "power_in"))
      (node (ref "U3") (pin "6") (pinfunction "VDD_6") (pintype "power_in"))
      (node (ref "U4") (pin "6") (pinfunction "VDD_6") (pintype "power_in"))
      (node (ref "U5") (pin "6") (pinfunction "VDD_6") (pintype "power_in"))
      (node (ref "U6") (pin "6") (pinfunction "VDD_6") (pintype "power_in"))
      (node (ref "U8") (pin "1") (pinfunction "VIN_1") (pintype "bidirectional"))
      (node (ref "U8B") (pin "5") (pinfunction "IN_5") (pintype "input"))
      (node (ref "U9") (pin "4") (pinfunction "V+_4") (pintype "power_in"))
    )
    (net (code "4") (name "/AGND") (class "Default")
      (node (ref "U$1") (pin "AGND") (pinfunction "AGND_AGND") (pintype "power_in"))
    )
    (net (code "5") (name "/AVDD") (class "Default")
      (node (ref "U$1") (pin "AVDD") (pinfunction "AVDD_AVDD") (pintype "power_in"))
    )
    (net (code "6") (name "/CANH") (class "Default")
      (node (ref "J1") (pin "1") (pinfunction "1_1") (pintype "passive"))
      (node (ref "J2") (pin "1") (pinfunction "1_1") (pintype "passive"))
      (node (ref "U7") (pin "7") (pinfunction "CANH_7") (pintype "bidirectional"))
      (node (ref "U7B") (pin "7") (pinfunction "CANH_7") (pintype "bidirectional"))
    )
    (net (code "7") (name "/CANL") (class "Default")
      (node (ref "J1") (pin "2") (pinfunction "2_2") (pintype "passive"))
      (node (ref "J2") (pin "2") (pinfunction "2_2") (pintype "passive"))
      (node (ref "U7") (pin "6") (pinfunction "CANL_6") (pintype "bidirectional"))
      (node (ref "U7B") (pin "6") (pinfunction "CANL_6") (pintype "bidirectional"))
    )
    (net (code "8") (name "/GND4") (class "Default")
      (node (ref "U$1") (pin "GND4") (pinfunction "GND4_GND4") (pintype "power_in"))
    )
    (net (code "9") (name "/PWR_POS") (class "Default")
      (node (ref "J1") (pin "8") (pinfunction "8_8") (pintype "passive"))
      (node (ref "J2") (pin "8") (pinfunction "8_8") (pintype "passive"))
      (node (ref "R40") (pin "2") (pinfunction "2_2") (pintype "passive"))
    )
    (net (code "10") (name "/U5V") (class "Default")
      (node (ref "U$1") (pin "U5V") (pinfunction "U5V_U5V") (pintype "power_in"))
    )
    (net (code "11") (name "/VBAT") (class "Default")
      (node (ref "U$1") (pin "VBAT") (pinfunction "VBAT_VBAT") (pintype "power_in"))
    )
    (net (code "12") (name "/VDD") (class "Default")
      (node (ref "U$1") (pin "VDD") (pinfunction "VDD_VDD") (pintype "power_in"))
    )
    (net (code "13") (name "CANRX") (class "Default")
      (node (ref "U$1") (pin "PB8") (pinfunction "PB8_PB8") (pintype "bidirectional"))
      (node (ref "U7") (pin "4") (pinfunction "RXD_4") (pintype "output"))
      (node (ref "U7B") (pin "4") (pinfunction "RXD_4") (pintype "bidirectional"))
    )
    (net (code "14") (name "CANTX") (class "Default")
      (node (ref "U$1") (pin "PB9") (pinfunction "PB9_PB9") (pintype "bidirectional"))
      (node (ref "U7") (pin "1") (pinfunction "TXD_1") (pintype "input"))
      (node (ref "U7B") (pin "1") (pinfunction "TXD_1") (pintype "bidirectional"))
    )
    (net (code "15") (name "E_CS") (class "Default")
      (node (ref "JP2") (pin "4") (pinfunction "4_4") (pintype "passive"))
      (node (ref "R23") (pin "2") (pinfunction "2_2") (pintype "passive"))
      (node (ref "U$1") (pin "PC10") (pinfunction "PC10_PC10") (pintype "bidirectional"))
    )
    (net (code "16") (name "E_LAT") (class "Default")
      (node (ref "JP2") (pin "5") (pinfunction "5_5") (pintype "passive"))
      (node (ref "R22") (pin "2") (pinfunction "2_2") (pintype "passive"))
      (node (ref "U$1") (pin "PC11") (pinfunction "PC11_PC11") (pintype "bidirectional"))
    )
    (net (code "17") (name "GND") (class "Default")
      (node (ref "C1") (pin "2") (pinfunction "2_2") (pintype "passive"))
      (node (ref "C10") (pin "2") (pinfunction "2_2") (pintype "passive"))
      (node (ref "C11") (pin "2") (pinfunction "2_2") (pintype "passive"))
      (node (ref "C2") (pin "-") (pinfunction "-_-") (pintype "passive"))
      (node (ref "C3") (pin "2") (pinfunction "2_2") (pintype "passive"))
      (node (ref "C4") (pin "2") (pinfunction "2_2") (pintype "passive"))
      (node (ref "C5") (pin "2") (pinfunction "2_2") (pintype "passive"))
      (node (ref "C6") (pin "2") (pinfunction "2_2") (pintype "passive"))
      (node (ref "C7") (pin "2") (pinfunction "2_2") (pintype "passive"))
      (node (ref "C8") (pin "2") (pinfunction "2_2") (pintype "passive"))
      (node (ref "C9") (pin "2") (pinfunction "2_2") (pintype "passive"))
      (node (ref "D1") (pin "A") (pinfunction "A_A") (pintype "passive"))
      (node (ref "D3") (pin "A") (pinfunction "A_A") (pintype "passive"))
      (node (ref "J1") (pin "3") (pinfunction "3_3") (pintype "passive"))
      (node (ref "J1") (pin "6") (pinfunction "6_6") (pintype "passive"))
      (node (ref "J1") (pin "7") (pinfunction "7_7") (pintype "passive"))
      (node (ref "J2") (pin "3") (pinfunction "3_3") (pintype "passive"))
      (node (ref "J2") (pin "6") (pinfunction "6_6") (pintype "passive"))
      (node (ref "J2") (pin "7") (pinfunction "7_7") (pintype "passive"))
      (node (ref "J3") (pin "2") (pinfunction "2_2") (pintype "passive"))
      (node (ref "J3") (pin "3") (pinfunction "3_3") (pintype "passive"))
      (node (ref "JP1") (pin "4") (pinfunction "4_4") (pintype "passive"))
      (node (ref "JP2") (pin "8") (pinfunction "8_8") (pintype "passive"))
      (node (ref "JP5") (pin "5") (pinfunction "5_5") (pintype "passive"))
      (node (ref "JP5") (pin "6") (pinfunction "6_6") (pintype "passive"))
      (node (ref "JP6") (pin "5") (pinfunction "5_5") (pintype "passive"))
      (node (ref "JP6") (pin "6") (pinfunction "6_6") (pintype "passive"))
      (node (ref "JP7") (pin "5") (pinfunction "5_5") (pintype "passive"))
      (node (ref "JP7") (pin "6") (pinfunction "6_6") (pintype "passive"))
      (node (ref "JP8") (pin "5") (pinfunction "5_5") (pintype "passive"))
      (node (ref "JP8") (pin "6") (pinfunction "6_6") (pintype "passive"))
      (node (ref "PORTA") (pin "5") (pinfunction "5_5") (pintype "passive"))
      (node (ref "PORTB") (pin "5") (pinfunction "5_5") (pintype "passive"))
      (node (ref "PORTC") (pin "5") (pinfunction "5_5") (pintype "passive"))
      (node (ref "Q1") (pin "2") (pinfunction "S_2") (pintype "passive"))
      (node (ref "Q10") (pin "2") (pinfunction "S_2") (pintype "passive"))
      (node (ref "Q11") (pin "2") (pinfunction "S_2") (pintype "passive"))
      (node (ref "Q12") (pin "2") (pinfunction "S_2") (pintype "passive"))
      (node (ref "Q13") (pin "2") (pinfunction "S_2") (pintype "passive"))
      (node (ref "Q14") (pin "2") (pinfunction "S_2") (pintype "passive"))
      (node (ref "Q15") (pin "2") (pinfunction "S_2") (pintype "passive"))
      (node (ref "Q16") (pin "2") (pinfunction "S_2") (pintype "passive"))
      (node (ref "Q2") (pin "2") (pinfunction "S_2") (pintype "passive"))
      (node (ref "Q3") (pin "2") (pinfunction "S_2") (pintype "passive"))
      (node (ref "Q4") (pin "2") (pinfunction "S_2") (pintype "passive"))
      (node (ref "Q5") (pin "2") (pinfunction "S_2") (pintype "passive"))
      (node (ref "Q6") (pin "2") (pinfunction "S_2") (pintype "passive"))
      (node (ref "Q7") (pin "2") (pinfunction "S_2") (pintype "passive"))
      (node (ref "Q8") (pin "2") (pinfunction "S_2") (pintype "passive"))
      (node (ref "Q9") (pin "2") (pinfunction "S_2") (pintype "passive"))
      (node (ref "R2") (pin "1") (pinfunction "1_1") (pintype "passive"))
      (node (ref "R61") (pin "2") (pinfunction "2_2") (pintype "passive"))
      (node (ref "SJ12") (pin "P$2") (pinfunction "2_P$2") (pintype "passive"))
      (node (ref "SJ3") (pin "2") (pinfunction "2_2") (pintype "passive"))
      (node (ref "SJ6") (pin "P$2") (pinfunction "2_P$2") (pintype "passive"))
      (node (ref "SJ9") (pin "2") (pinfunction "2_2") (pintype "passive"))
      (node (ref "U$1") (pin "GND3") (pinfunction "GND3_GND3") (pintype "power_in"))
      (node (ref "U$1") (pin "GND5") (pinfunction "GND5_GND5") (pintype "power_in"))
      (node (ref "U$1") (pin "GND6") (pinfunction "GND6_GND6") (pintype "power_in"))
      (node (ref "U$1") (pin "GND7") (pinfunction "GND7_GND7") (pintype "power_in"))
      (node (ref "U$1") (pin "GND8") (pinfunction "GND8_GND8") (pintype "power_in"))
      (node (ref "U1") (pin "6") (pinfunction "INH_6") (pintype "input"))
      (node (ref "U1") (pin "8") (pinfunction "GND_8") (pintype "power_in"))
      (node (ref "U10") (pin "11") (pinfunction "V-_11") (pintype "power_in"))
      (node (ref "U11") (pin "13") (pinfunction "G_13") (pintype "input"))
      (node (ref "U11") (pin "8") (pinfunction "GND_8") (pintype "power_in"))
      (node (ref "U13") (pin "13") (pinfunction "G_13") (pintype "input"))
      (node (ref "U13") (pin "8") (pinfunction "GND_8") (pintype "power_in"))
      (node (ref "U2") (pin "6") (pinfunction "INH_6") (pintype "input"))
      (node (ref "U2") (pin "8") (pinfunction "GND_8") (pintype "power_in"))
      (node (ref "U3") (pin "3") (pinfunction "VSS_3") (pintype "power_in"))
      (node (ref "U4") (pin "3") (pinfunction "VSS_3") (pintype "power_in"))
      (node (ref "U5") (pin "3") (pinfunction "VSS_3") (pintype "power_in"))
      (node (ref "U6") (pin "3") (pinfunction "VSS_3") (pintype "power_in"))
      (node (ref "U7") (pin "2") (pinfunction "GND_2") (pintype "power_in"))
      (node (ref "U7B") (pin "2") (pinfunction "VSS_2") (pintype "power_in"))
      (node (ref "U8") (pin "4") (pinfunction "SD_4") (pintype "bidirectional"))
      (node (ref "U8") (pin "5") (pinfunction "GND1_5") (pintype "power_in"))
      (node (ref "U8") (pin "6") (pinfunction "GND2_6") (pintype "power_in"))
      (node (ref "U8") (pin "7") (pinfunction "GND3_7") (pintype "power_in"))
      (node (ref "U8") (pin "8") (pinfunction "GND4_8") (pintype "power_in"))
      (node (ref "U8B") (pin "2") (pinfunction "GNDSIG_2") (pintype "input"))
      (node (ref "U8B") (pin "3") (pinfunction "~{ON/OFF}_3") (pintype "input"))
      (node (ref "U8B") (pin "4") (pinfunction "GND_4") (pintype "power_in"))
      (node (ref "U9") (pin "11") (pinfunction "V-_11") (pintype "power_in"))
      (node (ref "X6") (pin "2") (pinfunction "2_2") (pintype "passive"))
    )
    (net (code "18") (name "I2CSCL") (class "Default")
      (node (ref "JP1") (pin "1") (pinfunction "1_1") (pintype "passive"))
      (node (ref "R62") (pin "2") (pinfunction "2_2") (pintype "passive"))
      (node (ref "U$1") (pin "PB6") (pinfunction "PB6_PB6") (pintype "bidirectional"))
    )
    (net (code "19") (name "I2CSDA") (class "Default")
      (node (ref "JP1") (pin "2") (pinfunction "2_2") (pintype "passive"))
      (node (ref "R63") (pin "2") (pinfunction "2_2") (pintype "passive"))
      (node (ref "U$1") (pin "PB7") (pinfunction "PB7_PB7") (pintype "bidirectional"))
    )
    (net (code "20") (name "ILAT") (class "Default")
      (node (ref "U$1") (pin "PA6") (pinfunction "PA6_PA6") (pintype "bidirectional"))
      (node (ref "U1") (pin "15") (pinfunction "SH/~{LD}_15") (pintype "input"))
      (node (ref "U2") (pin "15") (pinfunction "SH/~{LD}_15") (pintype "input"))
    )
    (net (code "21") (name "MISO") (class "Default")
      (node (ref "JP2") (pin "1") (pinfunction "1_1") (pintype "passive"))
      (node (ref "U$1") (pin "PB4") (pinfunction "PB4_PB4") (pintype "bidirectional"))
    )
    (net (code "22") (name "MISO2") (class "Default")
      (node (ref "SJ13") (pin "P$2") (pinfunction "2_P$2") (pintype "passive"))
      (node (ref "SJ19") (pin "P$2") (pinfunction "2_P$2") (pintype "passive"))
      (node (ref "U$1") (pin "PC2") (pinfunction "PC2_PC2") (pintype "bidirectional"))
      (node (ref "U2") (pin "13") (pinfunction "QH_13") (pintype "output"))
    )
    (net (code "23") (name "MOSI") (class "Default")
      (node (ref "R20") (pin "1") (pinfunction "1_1") (pintype "passive"))
      (node (ref "SJ15") (pin "1") (pinfunction "1_1") (pintype "passive"))
      (node (ref "SJ17") (pin "P$2") (pinfunction "2_P$2") (pintype "passive"))
      (node (ref "U$1") (pin "PB5") (pinfunction "PB5_PB5") (pintype "bidirectional"))
      (node (ref "U11") (pin "14") (pinfunction "SER_14") (pintype "input"))
    )
    (net (code "24") (name "Net-(D2-PadA)") (class "Default")
      (node (ref "D2") (pin "A") (pinfunction "A_A") (pintype "passive"))
      (node (ref "D4") (pin "A") (pinfunction "A_A") (pintype "passive"))
      (node (ref "JP4") (pin "4") (pinfunction "4_4") (pintype "passive"))
    )
    (net (code "25") (name "Net-(D2-PadC)") (class "Default")
      (node (ref "D2") (pin "C") (pinfunction "C_C") (pintype "passive"))
      (node (ref "D4") (pin "C") (pinfunction "C_C") (pintype "passive"))
      (node (ref "JP4") (pin "1") (pinfunction "1_1") (pintype "passive"))
    )
    (net (code "26") (name "Net-(J1-Pad4)") (class "Default")
      (node (ref "J1") (pin "4") (pinfunction "4_4") (pintype "passive"))
      (node (ref "J2") (pin "4") (pinfunction "4_4") (pintype "passive"))
    )
    (net (code "27") (name "Net-(J1-Pad5)") (class "Default")
      (node (ref "J1") (pin "5") (pinfunction "5_5") (pintype "passive"))
      (node (ref "J2") (pin "5") (pinfunction "5_5") (pintype "passive"))
    )
    (net (code "28") (name "Net-(JP4-Pad3)") (class "Default")
      (node (ref "JP4") (pin "3") (pinfunction "3_3") (pintype "passive"))
      (node (ref "R40") (pin "1") (pinfunction "1_1") (pintype "passive"))
    )
    (net (code "29") (name "Net-(PORTA-Pad1)") (class "Default")
      (node (ref "PORTA") (pin "1") (pinfunction "1_1") (pintype "passive"))
      (node (ref "R44") (pin "2") (pinfunction "2_2") (pintype "passive"))
      (node (ref "R53") (pin "2") (pinfunction "2_2") (pintype "passive"))
      (node (ref "RN3") (pin "1") (pinfunction "1_1") (pintype "passive"))
      (node (ref "RN4") (pin "9") (pinfunction "9_9") (pintype "passive"))
      (node (ref "X1") (pin "1") (pinfunction "1_1") (pintype "passive"))
    )
    (net (code "30") (name "Net-(PORTB-Pad1)") (class "Default")
      (node (ref "PORTB") (pin "1") (pinfunction "1_1") (pintype "passive"))
      (node (ref "R35") (pin "2") (pinfunction "2_2") (pintype "passive"))
      (node (ref "R45") (pin "2") (pinfunction "2_2") (pintype "passive"))
      (node (ref "RN1") (pin "1") (pinfunction "1_1") (pintype "passive"))
      (node (ref "RN2") (pin "9") (pinfunction "9_9") (pintype "passive"))
      (node (ref "X2") (pin "1") (pinfunction "1_1") (pintype "passive"))
    )
    (net (code "31") (name "Net-(Q1-D)") (class "Default")
      (node (ref "Q1") (pin "3") (pinfunction "D_3") (pintype "passive"))
      (node (ref "U12") (pin "18") (pinfunction "O1_18") (pintype "open_collector"))
      (node (ref "X5") (pin "1") (pinfunction "1_1") (pintype "passive"))
    )
    (net (code "32") (name "Net-(Q1-G)") (class "Default")
      (node (ref "Q1") (pin "1") (pinfunction "G_1") (pintype "passive"))
      (node (ref "R3") (pin "2") (pinfunction "2_2") (pintype "passive"))
    )
    (net (code "33") (name "Net-(Q2-D)") (class "Default")
      (node (ref "Q2") (pin "3") (pinfunction "D_3") (pintype "passive"))
      (node (ref "U12") (pin "17") (pinfunction "O2_17") (pintype "open_collector"))
      (node (ref "X5") (pin "2") (pinfunction "2_2") (pintype "passive"))
    )
    (net (code "34") (name "Net-(Q2-G)") (class "Default")
      (node (ref "Q2") (pin "1") (pinfunction "G_1") (pintype "passive"))
      (node (ref "R4") (pin "2") (pinfunction "2_2") (pintype "passive"))
    )
    (net (code "35") (name "Net-(Q3-D)") (class "Default")
      (node (ref "Q3") (pin "3") (pinfunction "D_3") (pintype "passive"))
      (node (ref "U12") (pin "16") (pinfunction "O3_16") (pintype "open_collector"))
      (node (ref "X5") (pin "3") (pinfunction "3_3") (pintype "passive"))
    )
    (net (code "36") (name "Net-(Q3-G)") (class "Default")
      (node (ref "Q3") (pin "1") (pinfunction "G_1") (pintype "passive"))
      (node (ref "R5") (pin "2") (pinfunction "2_2") (pintype "passive"))
    )
    (net (code "37") (name "Net-(Q4-D)") (class "Default")
      (node (ref "Q4") (pin "3") (pinfunction "D_3") (pintype "passive"))
      (node (ref "U12") (pin "15") (pinfunction "O4_15") (pintype "open_collector"))
      (node (ref "X5") (pin "4") (pinfunction "4_4") (pintype "passive"))
    )
    (net (code "38") (name "Net-(Q4-G)") (class "Default")
      (node (ref "Q4") (pin "1") (pinfunction "G_1") (pintype "passive"))
      (node (ref "R6") (pin "2") (pinfunction "2_2") (pintype "passive"))
    )
    (net (code "39") (name "Net-(Q5-D)") (class "Default")
      (node (ref "Q5") (pin "3") (pinfunction "D_3") (pintype "passive"))
      (node (ref "U12") (pin "14") (pinfunction "O5_14") (pintype "open_collector"))
      (node (ref "X5") (pin "5") (pinfunction "5_5") (pintype "passive"))
    )
    (net (code "40") (name "Net-(Q5-G)") (class "Default")
      (node (ref "Q5") (pin "1") (pinfunction "G_1") (pintype "passive"))
      (node (ref "R7") (pin "2") (pinfunction "2_2") (pintype "passive"))
    )
    (net (code "41") (name "Net-(Q6-D)") (class "Default")
      (node (ref "Q6") (pin "3") (pinfunction "D_3") (pintype "passive"))
      (node (ref "U12") (pin "13") (pinfunction "O6_13") (pintype "open_collector"))
      (node (ref "X5") (pin "6") (pinfunction "6_6") (pintype "passive"))
    )
    (net (code "42") (name "Net-(Q6-G)") (class "Default")
      (node (ref "Q6") (pin "1") (pinfunction "G_1") (pintype "passive"))
      (node (ref "R8") (pin "2") (pinfunction "2_2") (pintype "passive"))
    )
    (net (code "43") (name "Net-(Q7-D)") (class "Default")
      (node (ref "Q7") (pin "3") (pinfunction "D_3") (pintype "passive"))
      (node (ref "U12") (pin "12") (pinfunction "O7_12") (pintype "open_collector"))
      (node (ref "X5") (pin "7") (pinfunction "7_7") (pintype "passive"))
    )
    (net (code "44") (name "Net-(Q7-G)") (class "Default")
      (node (ref "Q7") (pin "1") (pinfunction "G_1") (pintype "passive"))
      (node (ref "R9") (pin "2") (pinfunction "2_2") (pintype "passive"))
    )
    (net (code "45") (name "Net-(Q8-D)") (class "Default")
      (node (ref "Q8") (pin "3") (pinfunction "D_3") (pintype "passive"))
      (node (ref "U12") (pin "11") (pinfunction "O8_11") (pintype "open_collector"))
      (node (ref "X5") (pin "8") (pinfunction "8_8") (pintype "passive"))
    )
    (net (code "46") (name "Net-(Q8-G)") (class "Default")
      (node (ref "Q8") (pin "1") (pinfunction "G_1") (pintype "passive"))
      (node (ref "R10") (pin "2") (pinfunction "2_2") (pintype "passive"))
    )
    (net (code "47") (name "Net-(Q9-D)") (class "Default")
      (node (ref "Q9") (pin "3") (pinfunction "D_3") (pintype "passive"))
      (node (ref "U14") (pin "18") (pinfunction "O1_18") (pintype "open_collector"))
      (node (ref "X4") (pin "1") (pinfunction "1_1") (pintype "passive"))
    )
    (net (code "48") (name "Net-(Q9-G)") (class "Default")
      (node (ref "Q9") (pin "1") (pinfunction "G_1") (pintype "passive"))
      (node (ref "R11") (pin "2") (pinfunction "2_2") (pintype "passive"))
    )
    (net (code "49") (name "Net-(Q10-D)") (class "Default")
      (node (ref "Q10") (pin "3") (pinfunction "D_3") (pintype "passive"))
      (node (ref "U14") (pin "17") (pinfunction "O2_17") (pintype "open_collector"))
      (node (ref "X4") (pin "2") (pinfunction "2_2") (pintype "passive"))
    )
    (net (code "50") (name "Net-(Q10-G)") (class "Default")
      (node (ref "Q10") (pin "1") (pinfunction "G_1") (pintype "passive"))
      (node (ref "R12") (pin "2") (pinfunction "2_2") (pintype "passive"))
    )
    (net (code "51") (name "Net-(Q11-D)") (class "Default")
      (node (ref "Q11") (pin "3") (pinfunction "D_3") (pintype "passive"))
      (node (ref "U14") (pin "16") (pinfunction "O3_16") (pintype "open_collector"))
      (node (ref "X4") (pin "3") (pinfunction "3_3") (pintype "passive"))
    )
    (net (code "52") (name "Net-(Q11-G)") (class "Default")
      (node (ref "Q11") (pin "1") (pinfunction "G_1") (pintype "passive"))
      (node (ref "R13") (pin "2") (pinfunction "2_2") (pintype "passive"))
    )
    (net (code "53") (name "Net-(Q12-D)") (class "Default")
      (node (ref "Q12") (pin "3") (pinfunction "D_3") (pintype "passive"))
      (node (ref "U14") (pin "15") (pinfunction "O4_15") (pintype "open_collector"))
      (node (ref "X4") (pin "4") (pinfunction "4_4") (pintype "passive"))
    )
    (net (code "54") (name "Net-(Q12-G)") (class "Default")
      (node (ref "Q12") (pin "1") (pinfunction "G_1") (pintype "passive"))
      (node (ref "R14") (pin "2") (pinfunction "2_2") (pintype "passive"))
    )
    (net (code "55") (name "Net-(Q13-D)") (class "Default")
      (node (ref "Q13") (pin "3") (pinfunction "D_3") (pintype "passive"))
      (node (ref "U14") (pin "14") (pinfunction "O5_14") (pintype "open_collector"))
      (node (ref "X4") (pin "5") (pinfunction "5_5") (pintype "passive"))
    )
    (net (code "56") (name "Net-(Q13-G)") (class "Default")
      (node (ref "Q13") (pin "1") (pinfunction "G_1") (pintype "passive"))
      (node (ref "R15") (pin "2") (pinfunction "2_2") (pintype "passive"))
    )
    (net (code "57") (name "Net-(Q14-D)") (class "Default")
      (node (ref "Q14") (pin "3") (pinfunction "D_3") (pintype "passive"))
      (node (ref "U14") (pin "13") (pinfunction "O6_13") (pintype "open_collector"))
      (node (ref "X4") (pin "6") (pinfunction "6_6") (pintype "passive"))
    )
    (net (code "58") (name "Net-(Q14-G)") (class "Default")
      (node (ref "Q14") (pin "1") (pinfunction "G_1") (pintype "passive"))
      (node (ref "R16") (pin "2") (pinfunction "2_2") (pintype "passive"))
    )
    (net (code "59") (name "Net-(Q15-D)") (class "Default")
      (node (ref "Q15") (pin "3") (pinfunction "D_3") (pintype "passive"))
      (node (ref "U14") (pin "12") (pinfunction "O7_12") (pintype "open_collector"))
      (node (ref "X4") (pin "7") (pinfunction "7_7") (pintype "passive"))
    )
    (net (code "60") (name "Net-(Q15-G)") (class "Default")
      (node (ref "Q15") (pin "1") (pinfunction "G_1") (pintype "passive"))
      (node (ref "R17") (pin "2") (pinfunction "2_2") (pintype "passive"))
    )
    (net (code "61") (name "Net-(Q16-D)") (class "Default")
      (node (ref "Q16") (pin "3") (pinfunction "D_3") (pintype "passive"))
      (node (ref "U14") (pin "11") (pinfunction "O8_11") (pintype "open_collector"))
      (node (ref "X4") (pin "8") (pinfunction "8_8") (pintype "passive"))
    )
    (net (code "62") (name "Net-(Q16-G)") (class "Default")
      (node (ref "Q16") (pin "1") (pinfunction "G_1") (pintype "passive"))
      (node (ref "R18") (pin "2") (pinfunction "2_2") (pintype "passive"))
    )
    (net (code "63") (name "Net-(RN1A-2)") (class "Default")
      (node (ref "R35") (pin "1") (pinfunction "1_1") (pintype "passive"))
      (node (ref "RN1") (pin "16") (pinfunction "2_16") (pintype "passive"))
      (node (ref "U2") (pin "14") (pinfunction "H_14") (pintype "input"))
    )
    (net (code "64") (name "Net-(RN1B-1)") (class "Default")
      (node (ref "PORTB") (pin "2") (pinfunction "2_2") (pintype "passive"))
      (node (ref "R34") (pin "2") (pinfunction "2_2") (pintype "passive"))
      (node (ref "R46") (pin "2") (pinfunction "2_2") (pintype "passive"))
      (node (ref "RN1") (pin "2") (pinfunction "1_2") (pintype "passive"))
      (node (ref "RN2") (pin "8") (pinfunction "8_8") (pintype "passive"))
      (node (ref "X2") (pin "2") (pinfunction "2_2") (pintype "passive"))
    )
    (net (code "65") (name "Net-(RN1B-2)") (class "Default")
      (node (ref "R34") (pin "1") (pinfunction "1_1") (pintype "passive"))
      (node (ref "RN1") (pin "15") (pinfunction "2_15") (pintype "passive"))
      (node (ref "U2") (pin "12") (pinfunction "G_12") (pintype "input"))
    )
    (net (code "66") (name "Net-(RN1C-1)") (class "Default")
      (node (ref "PORTB") (pin "3") (pinfunction "3_3") (pintype "passive"))
      (node (ref "R33") (pin "2") (pinfunction "2_2") (pintype "passive"))
      (node (ref "R47") (pin "2") (pinfunction "2_2") (pintype "passive"))
      (node (ref "RN1") (pin "3") (pinfunction "1_3") (pintype "passive"))
      (node (ref "RN2") (pin "7") (pinfunction "7_7") (pintype "passive"))
      (node (ref "X2") (pin "3") (pinfunction "3_3") (pintype "passive"))
    )
    (net (code "67") (name "Net-(RN1C-2)") (class "Default")
      (node (ref "R33") (pin "1") (pinfunction "1_1") (pintype "passive"))
      (node (ref "RN1") (pin "14") (pinfunction "2_14") (pintype "passive"))
      (node (ref "U2") (pin "11") (pinfunction "F_11") (pintype "input"))
    )
    (net (code "68") (name "Net-(RN1D-1)") (class "Default")
      (node (ref "PORTB") (pin "4") (pinfunction "4_4") (pintype "passive"))
      (node (ref "R32") (pin "2") (pinfunction "2_2") (pintype "passive"))
      (node (ref "R48") (pin "2") (pinfunction "2_2") (pintype "passive"))
      (node (ref "RN1") (pin "4") (pinfunction "1_4") (pintype "passive"))
      (node (ref "RN2") (pin "6") (pinfunction "6_6") (pintype "passive"))
      (node (ref "X2") (pin "4") (pinfunction "4_4") (pintype "passive"))
    )
    (net (code "69") (name "Net-(RN1D-2)") (class "Default")
      (node (ref "R32") (pin "1") (pinfunction "1_1") (pintype "passive"))
      (node (ref "RN1") (pin "13") (pinfunction "2_13") (pintype "passive"))
      (node (ref "U2") (pin "10") (pinfunction "E_10") (pintype "input"))
    )
    (net (code "70") (name "Net-(RN1E-1)") (class "Default")
      (node (ref "PORTB") (pin "7") (pinfunction "7_7") (pintype "passive"))
      (node (ref "R31") (pin "2") (pinfunction "2_2") (pintype "passive"))
      (node (ref "R49") (pin "2") (pinfunction "2_2") (pintype "passive"))
      (node (ref "RN1") (pin "5") (pinfunction "1_5") (pintype "passive"))
      (node (ref "RN2") (pin "5") (pinfunction "5_5") (pintype "passive"))
      (node (ref "X2") (pin "5") (pinfunction "5_5") (pintype "passive"))
    )
    (net (code "71") (name "Net-(RN1E-2)") (class "Default")
      (node (ref "R31") (pin "1") (pinfunction "1_1") (pintype "passive"))
      (node (ref "RN1") (pin "12") (pinfunction "2_12") (pintype "passive"))
      (node (ref "U2") (pin "5") (pinfunction "D_5") (pintype "input"))
    )
    (net (code "72") (name "Net-(RN1F-1)") (class "Default")
      (node (ref "PORTB") (pin "8") (pinfunction "8_8") (pintype "passive"))
      (node (ref "R30") (pin "2") (pinfunction "2_2") (pintype "passive"))
      (node (ref "R50") (pin "2") (pinfunction "2_2") (pintype "passive"))
      (node (ref "RN1") (pin "6") (pinfunction "1_6") (pintype "passive"))
      (node (ref "RN2") (pin "4") (pinfunction "4_4") (pintype "passive"))
      (node (ref "X2") (pin "6") (pinfunction "6_6") (pintype "passive"))
    )
    (net (code "73") (name "Net-(RN1F-2)") (class "Default")
      (node (ref "R30") (pin "1") (pinfunction "1_1") (pintype "passive"))
      (node (ref "RN1") (pin "11") (pinfunction "2_11") (pintype "passive"))
      (node (ref "U2") (pin "4") (pinfunction "C_4") (pintype "input"))
    )
    (net (code "74") (name "Net-(RN1G-1)") (class "Default")
      (node (ref "PORTB") (pin "9") (pinfunction "9_9") (pintype "passive"))
      (node (ref "R29") (pin "2") (pinfunction "2_2") (pintype "passive"))
      (node (ref "R51") (pin "2") (pinfunction "2_2") (pintype "passive"))
      (node (ref "RN1") (pin "7") (pinfunction "1_7") (pintype "passive"))
      (node (ref "RN2") (pin "3") (pinfunction "3_3") (pintype "passive"))
      (node (ref "X2") (pin "7") (pinfunction "7_7") (pintype "passive"))
    )
    (net (code "75") (name "Net-(RN1G-2)") (class "Default")
      (node (ref "R29") (pin "1") (pinfunction "1_1") (pintype "passive"))
      (node (ref "RN1") (pin "10") (pinfunction "2_10") (pintype "passive"))
      (node (ref "U2") (pin "3") (pinfunction "B_3") (pintype "input"))
    )
    (net (code "76") (name "Net-(RN1H-1)") (class "Default")
      (node (ref "PORTB") (pin "10") (pinfunction "10_10") (pintype "passive"))
      (node (ref "R28") (pin "2") (pinfunction "2_2") (pintype "passive"))
      (node (ref "R52") (pin "2") (pinfunction "2_2") (pintype "passive"))
      (node (ref "RN1") (pin "8") (pinfunction "1_8") (pintype "passive"))
      (node (ref "RN2") (pin "2") (pinfunction "2_2") (pintype "passive"))
      (node (ref "X2") (pin "8") (pinfunction "8_8") (pintype "passive"))
    )
    (net (code "77") (name "Net-(RN1H-2)") (class "Default")
      (node (ref "R28") (pin "1") (pinfunction "1_1") (pintype "passive"))
      (node (ref "RN1") (pin "9") (pinfunction "2_9") (pintype "passive"))
      (node (ref "U2") (pin "2") (pinfunction "A_2") (pintype "input"))
    )
    (net (code "78") (name "Net-(RN3A-2)") (class "Default")
      (node (ref "R44") (pin "1") (pinfunction "1_1") (pintype "passive"))
      (node (ref "RN3") (pin "16") (pinfunction "2_16") (pintype "passive"))
      (node (ref "U1") (pin "14") (pinfunction "H_14") (pintype "input"))
    )
    (net (code "79") (name "Net-(RN3B-1)") (class "Default")
      (node (ref "PORTA") (pin "2") (pinfunction "2_2") (pintype "passive"))
      (node (ref "R43") (pin "2") (pinfunction "2_2") (pintype "passive"))
      (node (ref "R54") (pin "2") (pinfunction "2_2") (pintype "passive"))
      (node (ref "RN3") (pin "2") (pinfunction "1_2") (pintype "passive"))
      (node (ref "RN4") (pin "8") (pinfunction "8_8") (pintype "passive"))
      (node (ref "X1") (pin "2") (pinfunction "2_2") (pintype "passive"))
    )
    (net (code "80") (name "Net-(RN3B-2)") (class "Default")
      (node (ref "R43") (pin "1") (pinfunction "1_1") (pintype "passive"))
      (node (ref "RN3") (pin "15") (pinfunction "2_15") (pintype "passive"))
      (node (ref "U1") (pin "12") (pinfunction "G_12") (pintype "input"))
    )
    (net (code "81") (name "Net-(RN3C-1)") (class "Default")
      (node (ref "PORTA") (pin "3") (pinfunction "3_3") (pintype "passive"))
      (node (ref "R42") (pin "2") (pinfunction "2_2") (pintype "passive"))
      (node (ref "R55") (pin "2") (pinfunction "2_2") (pintype "passive"))
      (node (ref "RN3") (pin "3") (pinfunction "1_3") (pintype "passive"))
      (node (ref "RN4") (pin "7") (pinfunction "7_7") (pintype "passive"))
      (node (ref "X1") (pin "3") (pinfunction "3_3") (pintype "passive"))
    )
    (net (code "82") (name "Net-(RN3C-2)") (class "Default")
      (node (ref "R42") (pin "1") (pinfunction "1_1") (pintype "passive"))
      (node (ref "RN3") (pin "14") (pinfunction "2_14") (pintype "passive"))
      (node (ref "U1") (pin "11") (pinfunction "F_11") (pintype "input"))
    )
    (net (code "83") (name "Net-(RN3D-1)") (class "Default")
      (node (ref "PORTA") (pin "4") (pinfunction "4_4") (pintype "passive"))
      (node (ref "R41") (pin "2") (pinfunction "2_2") (pintype "passive"))
      (node (ref "R56") (pin "2") (pinfunction "2_2") (pintype "passive"))
      (node (ref "RN3") (pin "4") (pinfunction "1_4") (pintype "passive"))
      (node (ref "RN4") (pin "6") (pinfunction "6_6") (pintype "passive"))
      (node (ref "X1") (pin "4") (pinfunction "4_4") (pintype "passive"))
    )
    (net (code "84") (name "Net-(RN3D-2)") (class "Default")
      (node (ref "R41") (pin "1") (pinfunction "1_1") (pintype "passive"))
      (node (ref "RN3") (pin "13") (pinfunction "2_13") (pintype "passive"))
      (node (ref "U1") (pin "10") (pinfunction "E_10") (pintype "input"))
    )
    (net (code "85") (name "Net-(RN3E-1)") (class "Default")
      (node (ref "PORTA") (pin "7") (pinfunction "7_7") (pintype "passive"))
      (node (ref "R39") (pin "2") (pinfunction "2_2") (pintype "passive"))
      (node (ref "R57") (pin "2") (pinfunction "2_2") (pintype "passive"))
      (node (ref "RN3") (pin "5") (pinfunction "1_5") (pintype "passive"))
      (node (ref "RN4") (pin "5") (pinfunction "5_5") (pintype "passive"))
      (node (ref "X1") (pin "5") (pinfunction "5_5") (pintype "passive"))
    )
    (net (code "86") (name "Net-(RN3E-2)") (class "Default")
      (node (ref "R39") (pin "1") (pinfunction "1_1") (pintype "passive"))
      (node (ref "RN3") (pin "12") (pinfunction "2_12") (pintype "passive"))
      (node (ref "U1") (pin "5") (pinfunction "D_5") (pintype "input"))
    )
    (net (code "87") (name "Net-(RN3F-1)") (class "Default")
      (node (ref "PORTA") (pin "8") (pinfunction "8_8") (pintype "passive"))
      (node (ref "R38") (pin "2") (pinfunction "2_2") (pintype "passive"))
      (node (ref "R58") (pin "2") (pinfunction "2_2") (pintype "passive"))
      (node (ref "RN3") (pin "6") (pinfunction "1_6") (pintype "passive"))
      (node (ref "RN4") (pin "4") (pinfunction "4_4") (pintype "passive"))
      (node (ref "X1") (pin "6") (pinfunction "6_6") (pintype "passive"))
    )
    (net (code "88") (name "Net-(RN3F-2)") (class "Default")
      (node (ref "R38") (pin "1") (pinfunction "1_1") (pintype "passive"))
      (node (ref "RN3") (pin "11") (pinfunction "2_11") (pintype "passive"))
      (node (ref "U1") (pin "4") (pinfunction "C_4") (pintype "input"))
    )
    (net (code "89") (name "Net-(RN3G-1)") (class "Default")
      (node (ref "PORTA") (pin "9") (pinfunction "9_9") (pintype "passive"))
      (node (ref "R37") (pin "2") (pinfunction "2_2") (pintype "passive"))
      (node (ref "R59") (pin "2") (pinfunction "2_2") (pintype "passive"))
      (node (ref "RN3") (pin "7") (pinfunction "1_7") (pintype "passive"))
      (node (ref "RN4") (pin "3") (pinfunction "3_3") (pintype "passive"))
      (node (ref "X1") (pin "7") (pinfunction "7_7") (pintype "passive"))
    )
    (net (code "90") (name "Net-(RN3G-2)") (class "Default")
      (node (ref "R37") (pin "1") (pinfunction "1_1") (pintype "passive"))
      (node (ref "RN3") (pin "10") (pinfunction "2_10") (pintype "passive"))
      (node (ref "U1") (pin "3") (pinfunction "B_3") (pintype "input"))
    )
    (net (code "91") (name "Net-(RN3H-1)") (class "Default")
      (node (ref "PORTA") (pin "10") (pinfunction "10_10") (pintype "passive"))
      (node (ref "R36") (pin "2") (pinfunction "2_2") (pintype "passive"))
      (node (ref "R60") (pin "2") (pinfunction "2_2") (pintype "passive"))
      (node (ref "RN3") (pin "8") (pinfunction "1_8") (pintype "passive"))
      (node (ref "RN4") (pin "2") (pinfunction "2_2") (pintype "passive"))
      (node (ref "X1") (pin "8") (pinfunction "8_8") (pintype "passive"))
    )
    (net (code "92") (name "Net-(RN3H-2)") (class "Default")
      (node (ref "R36") (pin "1") (pinfunction "1_1") (pintype "passive"))
      (node (ref "RN3") (pin "9") (pinfunction "2_9") (pintype "passive"))
      (node (ref "U1") (pin "2") (pinfunction "A_2") (pintype "input"))
    )
    (net (code "93") (name "Net-(SJ1-1)") (class "Default")
      (node (ref "SJ1") (pin "P$1") (pinfunction "1_P$1") (pintype "passive"))
      (node (ref "SJ2") (pin "P$1") (pinfunction "1_P$1") (pintype "passive"))
      (node (ref "SJ3") (pin "1") (pinfunction "1_1") (pintype "passive"))
      (node (ref "U12") (pin "9") (pinfunction "GND_9") (pintype "power_in"))
    )
    (net (code "94") (name "Net-(SJ4-1)") (class "Default")
      (node (ref "SJ4") (pin "P$1") (pinfunction "1_P$1") (pintype "passive"))
      (node (ref "SJ5") (pin "P$1") (pinfunction "1_P$1") (pintype "passive"))
      (node (ref "SJ6") (pin "P$1") (pinfunction "1_P$1") (pintype "passive"))
      (node (ref "U12") (pin "10") (pinfunction "CD+_10") (pintype "passive"))
    )
    (net (code "95") (name "Net-(SJ7-1)") (class "Default")
      (node (ref "SJ7") (pin "P$1") (pinfunction "1_P$1") (pintype "passive"))
      (node (ref "SJ8") (pin "P$1") (pinfunction "1_P$1") (pintype "passive"))
      (node (ref "SJ9") (pin "1") (pinfunction "1_1") (pintype "passive"))
      (node (ref "U14") (pin "9") (pinfunction "GND_9") (pintype "power_in"))
    )
    (net (code "96") (name "Net-(SJ10-1)") (class "Default")
      (node (ref "SJ10") (pin "P$1") (pinfunction "1_P$1") (pintype "passive"))
      (node (ref "SJ11") (pin "P$1") (pinfunction "1_P$1") (pintype "passive"))
      (node (ref "SJ12") (pin "P$1") (pinfunction "1_P$1") (pintype "passive"))
      (node (ref "U14") (pin "10") (pinfunction "CD+_10") (pintype "passive"))
    )
    (net (code "97") (name "Net-(SJ13-1)") (class "Default")
      (node (ref "SJ13") (pin "P$1") (pinfunction "1_P$1") (pintype "passive"))
      (node (ref "U$1") (pin "PB14") (pinfunction "PB14_PB14") (pintype "bidirectional"))
    )
    (net (code "98") (name "Net-(SJ14-1)") (class "Default")
      (node (ref "SJ14") (pin "P$1") (pinfunction "1_P$1") (pintype "passive"))
      (node (ref "U$1") (pin "VIN2") (pinfunction "VIN2_VIN2") (pintype "power_in"))
    )
    (net (code "99") (name "Net-(SJ16-2)") (class "Default")
      (node (ref "JP2") (pin "2") (pinfunction "2_2") (pintype "passive"))
      (node (ref "SJ15") (pin "2") (pinfunction "2_2") (pintype "passive"))
      (node (ref "SJ16") (pin "P$2") (pinfunction "2_P$2") (pintype "passive"))
    )
    (net (code "100") (name "Net-(SJ18-2)") (class "Default")
      (node (ref "SJ18") (pin "P$2") (pinfunction "2_P$2") (pintype "passive"))
      (node (ref "U7") (pin "5") (pinfunction "VREF_5") (pintype "output"))
      (node (ref "U7B") (pin "5") (pinfunction "VREF_5") (pintype "bidirectional"))
    )
    (net (code "101") (name "Net-(U3A-O)") (class "Default")
      (node (ref "PORTC") (pin "1") (pinfunction "1_1") (pintype "passive"))
      (node (ref "U3") (pin "7") (pinfunction "O_7") (pintype "output"))
      (node (ref "U9") (pin "7") (pinfunction "OUT_7") (pintype "output"))
      (node (ref "X3") (pin "1") (pinfunction "1_1") (pintype "passive"))
    )
    (net (code "102") (name "Net-(U3B-O)") (class "Default")
      (node (ref "PORTC") (pin "2") (pinfunction "2_2") (pintype "passive"))
      (node (ref "U3") (pin "5") (pinfunction "O_5") (pintype "output"))
      (node (ref "U9") (pin "8") (pinfunction "OUT_8") (pintype "output"))
      (node (ref "X3") (pin "2") (pinfunction "2_2") (pintype "passive"))
    )
    (net (code "103") (name "Net-(U4A-O)") (class "Default")
      (node (ref "PORTC") (pin "4") (pinfunction "4_4") (pintype "passive"))
      (node (ref "U4") (pin "7") (pinfunction "O_7") (pintype "output"))
      (node (ref "U9") (pin "14") (pinfunction "OUT_14") (pintype "output"))
      (node (ref "X3") (pin "4") (pinfunction "4_4") (pintype "passive"))
    )
    (net (code "104") (name "Net-(U4B-O)") (class "Default")
      (node (ref "PORTC") (pin "3") (pinfunction "3_3") (pintype "passive"))
      (node (ref "U4") (pin "5") (pinfunction "O_5") (pintype "output"))
      (node (ref "U9") (pin "1") (pinfunction "OUT_1") (pintype "output"))
      (node (ref "X3") (pin "3") (pinfunction "3_3") (pintype "passive"))
    )
    (net (code "105") (name "Net-(U7-RS)") (class "Default")
      (node (ref "R61") (pin "1") (pinfunction "1_1") (pintype "passive"))
      (node (ref "U7") (pin "8") (pinfunction "RS_8") (pintype "input"))
      (node (ref "U7B") (pin "8") (pinfunction "RS_8") (pintype "bidirectional"))
    )
    (net (code "106") (name "Net-(U8-VOUT)") (class "Default")
      (node (ref "D1") (pin "C") (pinfunction "C_C") (pintype "passive"))
      (node (ref "D3") (pin "C") (pinfunction "C_C") (pintype "passive"))
      (node (ref "L1") (pin "2") (pinfunction "2_2") (pintype "passive"))
      (node (ref "U8") (pin "2") (pinfunction "VOUT_2") (pintype "bidirectional"))
      (node (ref "U8B") (pin "7") (pinfunction "OUT_7") (pintype "passive"))
    )
    (net (code "107") (name "Net-(U10A--IN)") (class "Default")
      (node (ref "R1") (pin "1") (pinfunction "1_1") (pintype "passive"))
      (node (ref "R2") (pin "2") (pinfunction "2_2") (pintype "passive"))
      (node (ref "U10") (pin "13") (pinfunction "-IN_13") (pintype "input"))
      (node (ref "U10") (pin "2") (pinfunction "-IN_2") (pintype "input"))
      (node (ref "U10") (pin "6") (pinfunction "-IN_6") (pintype "input"))
      (node (ref "U10") (pin "9") (pinfunction "-IN_9") (pintype "input"))
      (node (ref "U9") (pin "13") (pinfunction "-IN_13") (pintype "input"))
      (node (ref "U9") (pin "2") (pinfunction "-IN_2") (pintype "input"))
      (node (ref "U9") (pin "6") (pinfunction "-IN_6") (pintype "input"))
      (node (ref "U9") (pin "9") (pinfunction "-IN_9") (pintype "input"))
    )
    (net (code "108") (name "Net-(U10A-OUT)") (class "Default")
      (node (ref "PORTC") (pin "9") (pinfunction "9_9") (pintype "passive"))
      (node (ref "U10") (pin "1") (pinfunction "OUT_1") (pintype "output"))
      (node (ref "U6") (pin "5") (pinfunction "O_5") (pintype "output"))
      (node (ref "X3") (pin "7") (pinfunction "7_7") (pintype "passive"))
    )
    (net (code "109") (name "Net-(U10B-OUT)") (class "Default")
      (node (ref "PORTC") (pin "7") (pinfunction "7_7") (pintype "passive"))
      (node (ref "U10") (pin "7") (pinfunction "OUT_7") (pintype "output"))
      (node (ref "U5") (pin "7") (pinfunction "O_7") (pintype "output"))
      (node (ref "X3") (pin "5") (pinfunction "5_5") (pintype "passive"))
    )
    (net (code "110") (name "Net-(U10C-OUT)") (class "Default")
      (node (ref "PORTC") (pin "8") (pinfunction "8_8") (pintype "passive"))
      (node (ref "U10") (pin "8") (pinfunction "OUT_8") (pintype "output"))
      (node (ref "U5") (pin "5") (pinfunction "O_5") (pintype "output"))
      (node (ref "X3") (pin "6") (pinfunction "6_6") (pintype "passive"))
    )
    (net (code "111") (name "Net-(U10D-OUT)") (class "Default")
      (node (ref "PORTC") (pin "10") (pinfunction "10_10") (pintype "passive"))
      (node (ref "U10") (pin "14") (pinfunction "OUT_14") (pintype "output"))
      (node (ref "U6") (pin "7") (pinfunction "O_7") (pintype "output"))
      (node (ref "X3") (pin "8") (pinfunction "8_8") (pintype "passive"))
    )
    (net (code "112") (name "Net-(U11A-QA)") (class "Default")
      (node (ref "R3") (pin "1") (pinfunction "1_1") (pintype "passive"))
      (node (ref "U11") (pin "15") (pinfunction "QA_15") (pintype "tri_state"))
      (node (ref "U12") (pin "1") (pinfunction "I1_1") (pintype "input"))
    )
    (net (code "113") (name "Net-(U11A-QB)") (class "Default")
      (node (ref "R4") (pin "1") (pinfunction "1_1") (pintype "passive"))
      (node (ref "U11") (pin "1") (pinfunction "QB_1") (pintype "tri_state"))
      (node (ref "U12") (pin "2") (pinfunction "I2_2") (pintype "input"))
    )
    (net (code "114") (name "Net-(U11A-QC)") (class "Default")
      (node (ref "R5") (pin "1") (pinfunction "1_1") (pintype "passive"))
      (node (ref "U11") (pin "2") (pinfunction "QC_2") (pintype "tri_state"))
      (node (ref "U12") (pin "3") (pinfunction "I3_3") (pintype "input"))
    )
    (net (code "115") (name "Net-(U11A-QD)") (class "Default")
      (node (ref "R6") (pin "1") (pinfunction "1_1") (pintype "passive"))
      (node (ref "U11") (pin "3") (pinfunction "QD_3") (pintype "tri_state"))
      (node (ref "U12") (pin "4") (pinfunction "I4_4") (pintype "input"))
    )
    (net (code "116") (name "Net-(U11A-QE)") (class "Default")
      (node (ref "R7") (pin "1") (pinfunction "1_1") (pintype "passive"))
      (node (ref "U11") (pin "4") (pinfunction "QE_4") (pintype "tri_state"))
      (node (ref "U12") (pin "5") (pinfunction "I5_5") (pintype "input"))
    )
    (net (code "117") (name "Net-(U11A-QF)") (class "Default")
      (node (ref "R8") (pin "1") (pinfunction "1_1") (pintype "passive"))
      (node (ref "U11") (pin "5") (pinfunction "QF_5") (pintype "tri_state"))
      (node (ref "U12") (pin "6") (pinfunction "I6_6") (pintype "input"))
    )
    (net (code "118") (name "Net-(U11A-QG)") (class "Default")
      (node (ref "R9") (pin "1") (pinfunction "1_1") (pintype "passive"))
      (node (ref "U11") (pin "6") (pinfunction "QG_6") (pintype "tri_state"))
      (node (ref "U12") (pin "7") (pinfunction "I7_7") (pintype "input"))
    )
    (net (code "119") (name "Net-(U11A-QH)") (class "Default")
      (node (ref "R10") (pin "1") (pinfunction "1_1") (pintype "passive"))
      (node (ref "U11") (pin "7") (pinfunction "QH_7") (pintype "tri_state"))
      (node (ref "U12") (pin "8") (pinfunction "I8_8") (pintype "input"))
    )
    (net (code "120") (name "Net-(U13A-QA)") (class "Default")
      (node (ref "R11") (pin "1") (pinfunction "1_1") (pintype "passive"))
      (node (ref "U13") (pin "15") (pinfunction "QA_15") (pintype "tri_state"))
      (node (ref "U14") (pin "1") (pinfunction "I1_1") (pintype "input"))
    )
    (net (code "121") (name "Net-(U13A-QB)") (class "Default")
      (node (ref "R12") (pin "1") (pinfunction "1_1") (pintype "passive"))
      (node (ref "U13") (pin "1") (pinfunction "QB_1") (pintype "tri_state"))
      (node (ref "U14") (pin "2") (pinfunction "I2_2") (pintype "input"))
    )
    (net (code "122") (name "Net-(U13A-QC)") (class "Default")
      (node (ref "R13") (pin "1") (pinfunction "1_1") (pintype "passive"))
      (node (ref "U13") (pin "2") (pinfunction "QC_2") (pintype "tri_state"))
      (node (ref "U14") (pin "3") (pinfunction "I3_3") (pintype "input"))
    )
    (net (code "123") (name "Net-(U13A-QD)") (class "Default")
      (node (ref "R14") (pin "1") (pinfunction "1_1") (pintype "passive"))
      (node (ref "U13") (pin "3") (pinfunction "QD_3") (pintype "tri_state"))
      (node (ref "U14") (pin "4") (pinfunction "I4_4") (pintype "input"))
    )
    (net (code "124") (name "Net-(U13A-QE)") (class "Default")
      (node (ref "R15") (pin "1") (pinfunction "1_1") (pintype "passive"))
      (node (ref "U13") (pin "4") (pinfunction "QE_4") (pintype "tri_state"))
      (node (ref "U14") (pin "5") (pinfunction "I5_5") (pintype "input"))
    )
    (net (code "125") (name "Net-(U13A-QF)") (class "Default")
      (node (ref "R16") (pin "1") (pinfunction "1_1") (pintype "passive"))
      (node (ref "U13") (pin "5") (pinfunction "QF_5") (pintype "tri_state"))
      (node (ref "U14") (pin "6") (pinfunction "I6_6") (pintype "input"))
    )
    (net (code "126") (name "Net-(U13A-QG)") (class "Default")
      (node (ref "R17") (pin "1") (pinfunction "1_1") (pintype "passive"))
      (node (ref "U13") (pin "6") (pinfunction "QG_6") (pintype "tri_state"))
      (node (ref "U14") (pin "7") (pinfunction "I7_7") (pintype "input"))
    )
    (net (code "127") (name "Net-(U13A-QH)") (class "Default")
      (node (ref "R18") (pin "1") (pinfunction "1_1") (pintype "passive"))
      (node (ref "U13") (pin "7") (pinfunction "QH_7") (pintype "tri_state"))
      (node (ref "U14") (pin "8") (pinfunction "I8_8") (pintype "input"))
    )
    (net (code "128") (name "OLAT") (class "Default")
      (node (ref "R21") (pin "1") (pinfunction "1_1") (pintype "passive"))
      (node (ref "U$1") (pin "PA8") (pinfunction "PA8_PA8") (pintype "bidirectional"))
      (node (ref "U11") (pin "12") (pinfunction "RCK_12") (pintype "input"))
      (node (ref "U13") (pin "12") (pinfunction "RCK_12") (pintype "input"))
    )
    (net (code "129") (name "SCK") (class "Default")
      (node (ref "JP2") (pin "3") (pinfunction "3_3") (pintype "passive"))
      (node (ref "R19") (pin "1") (pinfunction "1_1") (pintype "passive"))
      (node (ref "U$1") (pin "PB3") (pinfunction "PB3_PB3") (pintype "bidirectional"))
      (node (ref "U11") (pin "11") (pinfunction "SCK_11") (pintype "input"))
      (node (ref "U13") (pin "11") (pinfunction "SCK_11") (pintype "input"))
    )
    (net (code "130") (name "SCK2") (class "Default")
      (node (ref "U$1") (pin "PB10") (pinfunction "PB10_PB10") (pintype "bidirectional"))
      (node (ref "U1") (pin "7") (pinfunction "CLK_7") (pintype "input"))
      (node (ref "U2") (pin "7") (pinfunction "CLK_7") (pintype "input"))
    )
    (net (code "131") (name "SLNK1") (class "Default")
      (node (ref "SJ17") (pin "P$1") (pinfunction "1_P$1") (pintype "passive"))
      (node (ref "U11") (pin "9") (pinfunction "QH*_9") (pintype "tri_state"))
      (node (ref "U13") (pin "14") (pinfunction "SER_14") (pintype "input"))
    )
    (net (code "132") (name "SLNK2") (class "Default")
      (node (ref "SJ16") (pin "P$1") (pinfunction "1_P$1") (pintype "passive"))
      (node (ref "U13") (pin "9") (pinfunction "QH*_9") (pintype "tri_state"))
    )
    (net (code "133") (name "SLNK3") (class "Default")
      (node (ref "SJ19") (pin "P$1") (pinfunction "1_P$1") (pintype "passive"))
      (node (ref "U1") (pin "13") (pinfunction "QH_13") (pintype "output"))
      (node (ref "U2") (pin "1") (pinfunction "SER_1") (pintype "input"))
    )
    (net (code "134") (name "SRV1") (class "Default")
      (node (ref "JP5") (pin "2") (pinfunction "2_2") (pintype "passive"))
      (node (ref "R24") (pin "2") (pinfunction "2_2") (pintype "passive"))
      (node (ref "U$1") (pin "PC9") (pinfunction "PC9_PC9") (pintype "bidirectional"))
    )
    (net (code "135") (name "SRV2") (class "Default")
      (node (ref "JP5") (pin "1") (pinfunction "1_1") (pintype "passive"))
      (node (ref "R25") (pin "2") (pinfunction "2_2") (pintype "passive"))
      (node (ref "U$1") (pin "PC7") (pinfunction "PC7_PC7") (pintype "bidirectional"))
    )
    (net (code "136") (name "SRV3") (class "Default")
      (node (ref "JP6") (pin "2") (pinfunction "2_2") (pintype "passive"))
      (node (ref "R26") (pin "2") (pinfunction "2_2") (pintype "passive"))
      (node (ref "U$1") (pin "PC8") (pinfunction "PC8_PC8") (pintype "bidirectional"))
    )
    (net (code "137") (name "SRV4") (class "Default")
      (node (ref "JP6") (pin "1") (pinfunction "1_1") (pintype "passive"))
      (node (ref "R27") (pin "2") (pinfunction "2_2") (pintype "passive"))
      (node (ref "U$1") (pin "PC6") (pinfunction "PC6_PC6") (pintype "bidirectional"))
    )
    (net (code "138") (name "SRV5") (class "Default")
      (node (ref "JP7") (pin "2") (pinfunction "2_2") (pintype "passive"))
      (node (ref "R64") (pin "2") (pinfunction "2_2") (pintype "passive"))
      (node (ref "U$1") (pin "PF1-PH1") (pinfunction "PF1-PH1_PF1-PH1") (pintype "bidirectional"))
    )
    (net (code "139") (name "SRV6") (class "Default")
      (node (ref "JP7") (pin "1") (pinfunction "1_1") (pintype "passive"))
      (node (ref "R65") (pin "2") (pinfunction "2_2") (pintype "passive"))
      (node (ref "U$1") (pin "PA15") (pinfunction "PA15_PA15") (pintype "bidirectional"))
    )
    (net (code "140") (name "SRV7") (class "Default")
      (node (ref "JP8") (pin "2") (pinfunction "2_2") (pintype "passive"))
      (node (ref "R66") (pin "2") (pinfunction "2_2") (pintype "passive"))
      (node (ref "U$1") (pin "PC12") (pinfunction "PC12_PC12") (pintype "bidirectional"))
    )
    (net (code "141") (name "SRV8") (class "Default")
      (node (ref "JP8") (pin "1") (pinfunction "1_1") (pintype "passive"))
      (node (ref "R67") (pin "2") (pinfunction "2_2") (pintype "passive"))
      (node (ref "U$1") (pin "PD2") (pinfunction "PD2_PD2") (pintype "bidirectional"))
    )
    (net (code "142") (name "TDRV1") (class "Default")
      (node (ref "U$1") (pin "PB12") (pinfunction "PB12_PB12") (pintype "bidirectional"))
      (node (ref "U10") (pin "12") (pinfunction "+IN_12") (pintype "input"))
      (node (ref "U6") (pin "2") (pinfunction "I_2") (pintype "input"))
    )
    (net (code "143") (name "TDRV2") (class "Default")
      (node (ref "U$1") (pin "PB2") (pinfunction "PB2_PB2") (pintype "bidirectional"))
      (node (ref "U10") (pin "3") (pinfunction "+IN_3") (pintype "input"))
      (node (ref "U6") (pin "4") (pinfunction "I_4") (pintype "input"))
    )
    (net (code "144") (name "TDRV3") (class "Default")
      (node (ref "U$1") (pin "PB15") (pinfunction "PB15_PB15") (pintype "bidirectional"))
      (node (ref "U10") (pin "10") (pinfunction "+IN_10") (pintype "input"))
      (node (ref "U5") (pin "4") (pinfunction "I_4") (pintype "input"))
    )
    (net (code "145") (name "TDRV4") (class "Default")
      (node (ref "U$1") (pin "PB1") (pinfunction "PB1_PB1") (pintype "bidirectional"))
      (node (ref "U10") (pin "5") (pinfunction "+IN_5") (pintype "input"))
      (node (ref "U5") (pin "2") (pinfunction "I_2") (pintype "input"))
    )
    (net (code "146") (name "TDRV5") (class "Default")
      (node (ref "U$1") (pin "PA0") (pinfunction "PA0_PA0") (pintype "bidirectional"))
      (node (ref "U4") (pin "2") (pinfunction "I_2") (pintype "input"))
      (node (ref "U9") (pin "12") (pinfunction "+IN_12") (pintype "input"))
    )
    (net (code "147") (name "TDRV6") (class "Default")
      (node (ref "U$1") (pin "PA4") (pinfunction "PA4_PA4") (pintype "bidirectional"))
      (node (ref "U4") (pin "4") (pinfunction "I_4") (pintype "input"))
      (node (ref "U9") (pin "3") (pinfunction "+IN_3") (pintype "input"))
    )
    (net (code "148") (name "TDRV7") (class "Default")
      (node (ref "U$1") (pin "PC3") (pinfunction "PC3_PC3") (pintype "bidirectional"))
      (node (ref "U3") (pin "4") (pinfunction "I_4") (pintype "input"))
      (node (ref "U9") (pin "10") (pinfunction "+IN_10") (pintype "input"))
    )
    (net (code "149") (name "TDRV8") (class "Default")
      (node (ref "U$1") (pin "PC0") (pinfunction "PC0_PC0") (pintype "bidirectional"))
      (node (ref "U3") (pin "2") (pinfunction "I_2") (pintype "input"))
      (node (ref "U9") (pin "5") (pinfunction "+IN_5") (pintype "input"))
    )
    (net (code "150") (name "V+") (class "Default")
      (node (ref "C1") (pin "1") (pinfunction "1_1") (pintype "passive"))
      (node (ref "C2") (pin "+") (pinfunction "+_+") (pintype "passive"))
      (node (ref "L1") (pin "1") (pinfunction "1_1") (pintype "passive"))
      (node (ref "U$1") (pin "E5V") (pinfunction "E5V_E5V") (pintype "power_in"))
      (node (ref "U8") (pin "3") (pinfunction "FB_3") (pintype "bidirectional"))
      (node (ref "U8B") (pin "1") (pinfunction "FB_1") (pintype "input"))
    )
    (net (code "151") (name "unconnected-(H1-MOUNT-PadB3,3)") (class "Default")
      (node (ref "H1") (pin "B3,3") (pinfunction "MOUNT_B3,3") (pintype "passive"))
    )
    (net (code "152") (name "unconnected-(H2-MOUNT-PadB3,3)") (class "Default")
      (node (ref "H2") (pin "B3,3") (pinfunction "MOUNT_B3,3") (pintype "passive"))
    )
    (net (code "153") (name "unconnected-(H3-MOUNT-PadB3,3)") (class "Default")
      (node (ref "H3") (pin "B3,3") (pinfunction "MOUNT_B3,3") (pintype "passive"))
    )
    (net (code "154") (name "unconnected-(H4-MOUNT-PadB3,3)") (class "Default")
      (node (ref "H4") (pin "B3,3") (pinfunction "MOUNT_B3,3") (pintype "passive"))
    )
    (net (code "155") (name "unconnected-(U$1-PadBOOT0)") (class "Default")
      (node (ref "U$1") (pin "BOOT0") (pinfunction "BOOT0_BOOT0") (pintype "bidirectional"))
    )
    (net (code "156") (name "unconnected-(U$1-PadIOREF2)") (class "Default")
      (node (ref "U$1") (pin "IOREF2") (pinfunction "IOREF2_IOREF2") (pintype "input"))
    )
    (net (code "157") (name "unconnected-(U$1-PadNC1-PF7)") (class "Default")
      (node (ref "U$1") (pin "NC1-PF7") (pinfunction "NC1-PF7_NC1-PF7") (pintype "bidirectional"))
    )
    (net (code "158") (name "unconnected-(U$1-PadNC2-PF6)") (class "Default")
      (node (ref "U$1") (pin "NC2-PF6") (pinfunction "NC2-PF6_NC2-PF6") (pintype "bidirectional"))
    )
    (net (code "159") (name "unconnected-(U$1-PadNC3)") (class "Default")
      (node (ref "U$1") (pin "NC3") (pinfunction "NC3_NC3") (pintype "no_connect"))
    )
    (net (code "160") (name "unconnected-(U$1-PadNC4)") (class "Default")
      (node (ref "U$1") (pin "NC4") (pinfunction "NC4_NC4") (pintype "no_connect"))
    )
    (net (code "161") (name "unconnected-(U$1-PadNC5-PD8)") (class "Default")
      (node (ref "U$1") (pin "NC5-PD8") (pinfunction "NC5-PD8_NC5-PD8") (pintype "bidirectional"))
    )
    (net (code "162") (name "unconnected-(U$1-PadNC6-PB11)") (class "Default")
      (node (ref "U$1") (pin "NC6-PB11") (pinfunction "NC6-PB11_NC6-PB11") (pintype "no_connect"))
    )
    (net (code "163") (name "unconnected-(U$1-PadNC7-PF5)") (class "Default")
      (node (ref "U$1") (pin "NC7-PF5") (pinfunction "NC7-PF5_NC7-PF5") (pintype "bidirectional"))
    )
    (net (code "164") (name "unconnected-(U$1-PadNC8-PF4)") (class "Default")
      (node (ref "U$1") (pin "NC8-PF4") (pinfunction "NC8-PF4_NC8-PF4") (pintype "bidirectional"))
    )
    (net (code "165") (name "unconnected-(U$1-PadNRESET)") (class "Default")
      (node (ref "U$1") (pin "NRESET") (pinfunction "NRESET_NRESET") (pintype "input"))
    )
    (net (code "166") (name "unconnected-(U$1-PadPA1)") (class "Default")
      (node (ref "U$1") (pin "PA1") (pinfunction "PA1_PA1") (pintype "bidirectional"))
    )
    (net (code "167") (name "unconnected-(U$1-PadPA2)") (class "Default")
      (node (ref "U$1") (pin "PA2") (pinfunction "PA2_PA2") (pintype "bidirectional"))
    )
    (net (code "168") (name "unconnected-(U$1-PadPA3)") (class "Default")
      (node (ref "U$1") (pin "PA3") (pinfunction "PA3_PA3") (pintype "bidirectional"))
    )
    (net (code "169") (name "unconnected-(U$1-PadPA5)") (class "Default")
      (node (ref "U$1") (pin "PA5") (pinfunction "PA5_PA5") (pintype "bidirectional"))
    )
    (net (code "170") (name "unconnected-(U$1-PadPA7)") (class "Default")
      (node (ref "U$1") (pin "PA7") (pinfunction "PA7_PA7") (pintype "bidirectional"))
    )
    (net (code "171") (name "unconnected-(U$1-PadPA9)") (class "Default")
      (node (ref "U$1") (pin "PA9") (pinfunction "PA9_PA9") (pintype "bidirectional"))
    )
    (net (code "172") (name "unconnected-(U$1-PadPA10)") (class "Default")
      (node (ref "U$1") (pin "PA10") (pinfunction "PA10_PA10") (pintype "bidirectional"))
    )
    (net (code "173") (name "unconnected-(U$1-PadPA11)") (class "Default")
      (node (ref "U$1") (pin "PA11") (pinfunction "PA11_PA11") (pintype "bidirectional"))
    )
    (net (code "174") (name "unconnected-(U$1-PadPA12)") (class "Default")
      (node (ref "U$1") (pin "PA12") (pinfunction "PA12_PA12") (pintype "bidirectional"))
    )
    (net (code "175") (name "unconnected-(U$1-PadPA13)") (class "Default")
      (node (ref "U$1") (pin "PA13") (pinfunction "PA13_PA13") (pintype "bidirectional"))
    )
    (net (code "176") (name "unconnected-(U$1-PadPA14)") (class "Default")
      (node (ref "U$1") (pin "PA14") (pinfunction "PA14_PA14") (pintype "bidirectional"))
    )
    (net (code "177") (name "unconnected-(U$1-PadPB0)") (class "Default")
      (node (ref "U$1") (pin "PB0") (pinfunction "PB0_PB0") (pintype "bidirectional"))
    )
    (net (code "178") (name "unconnected-(U$1-PadPB13)") (class "Default")
      (node (ref "U$1") (pin "PB13") (pinfunction "PB13_PB13") (pintype "bidirectional"))
    )
    (net (code "179") (name "unconnected-(U$1-PadPC1)") (class "Default")
      (node (ref "U$1") (pin "PC1") (pinfunction "PC1_PC1") (pintype "bidirectional"))
    )
    (net (code "180") (name "unconnected-(U$1-PadPC4)") (class "Default")
      (node (ref "U$1") (pin "PC4") (pinfunction "PC4_PC4") (pintype "bidirectional"))
    )
    (net (code "181") (name "unconnected-(U$1-PadPC5)") (class "Default")
      (node (ref "U$1") (pin "PC5") (pinfunction "PC5_PC5") (pintype "bidirectional"))
    )
    (net (code "182") (name "unconnected-(U$1-PadPC13)") (class "Default")
      (node (ref "U$1") (pin "PC13") (pinfunction "PC13_PC13") (pintype "bidirectional"))
    )
    (net (code "183") (name "unconnected-(U$1-PadPC14)") (class "Default")
      (node (ref "U$1") (pin "PC14") (pinfunction "PC14_PC14") (pintype "bidirectional"))
    )
    (net (code "184") (name "unconnected-(U$1-PadPC15)") (class "Default")
      (node (ref "U$1") (pin "PC15") (pinfunction "PC15_PC15") (pintype "bidirectional"))
    )
    (net (code "185") (name "unconnected-(U$1-PadPF0-PH0)") (class "Default")
      (node (ref "U$1") (pin "PF0-PH0") (pinfunction "PF0-PH0_PF0-PH0") (pintype "bidirectional"))
    )
  )
)
